# KELU1-0232.net
KiCad netlist of a schematic drawn in EAGLE
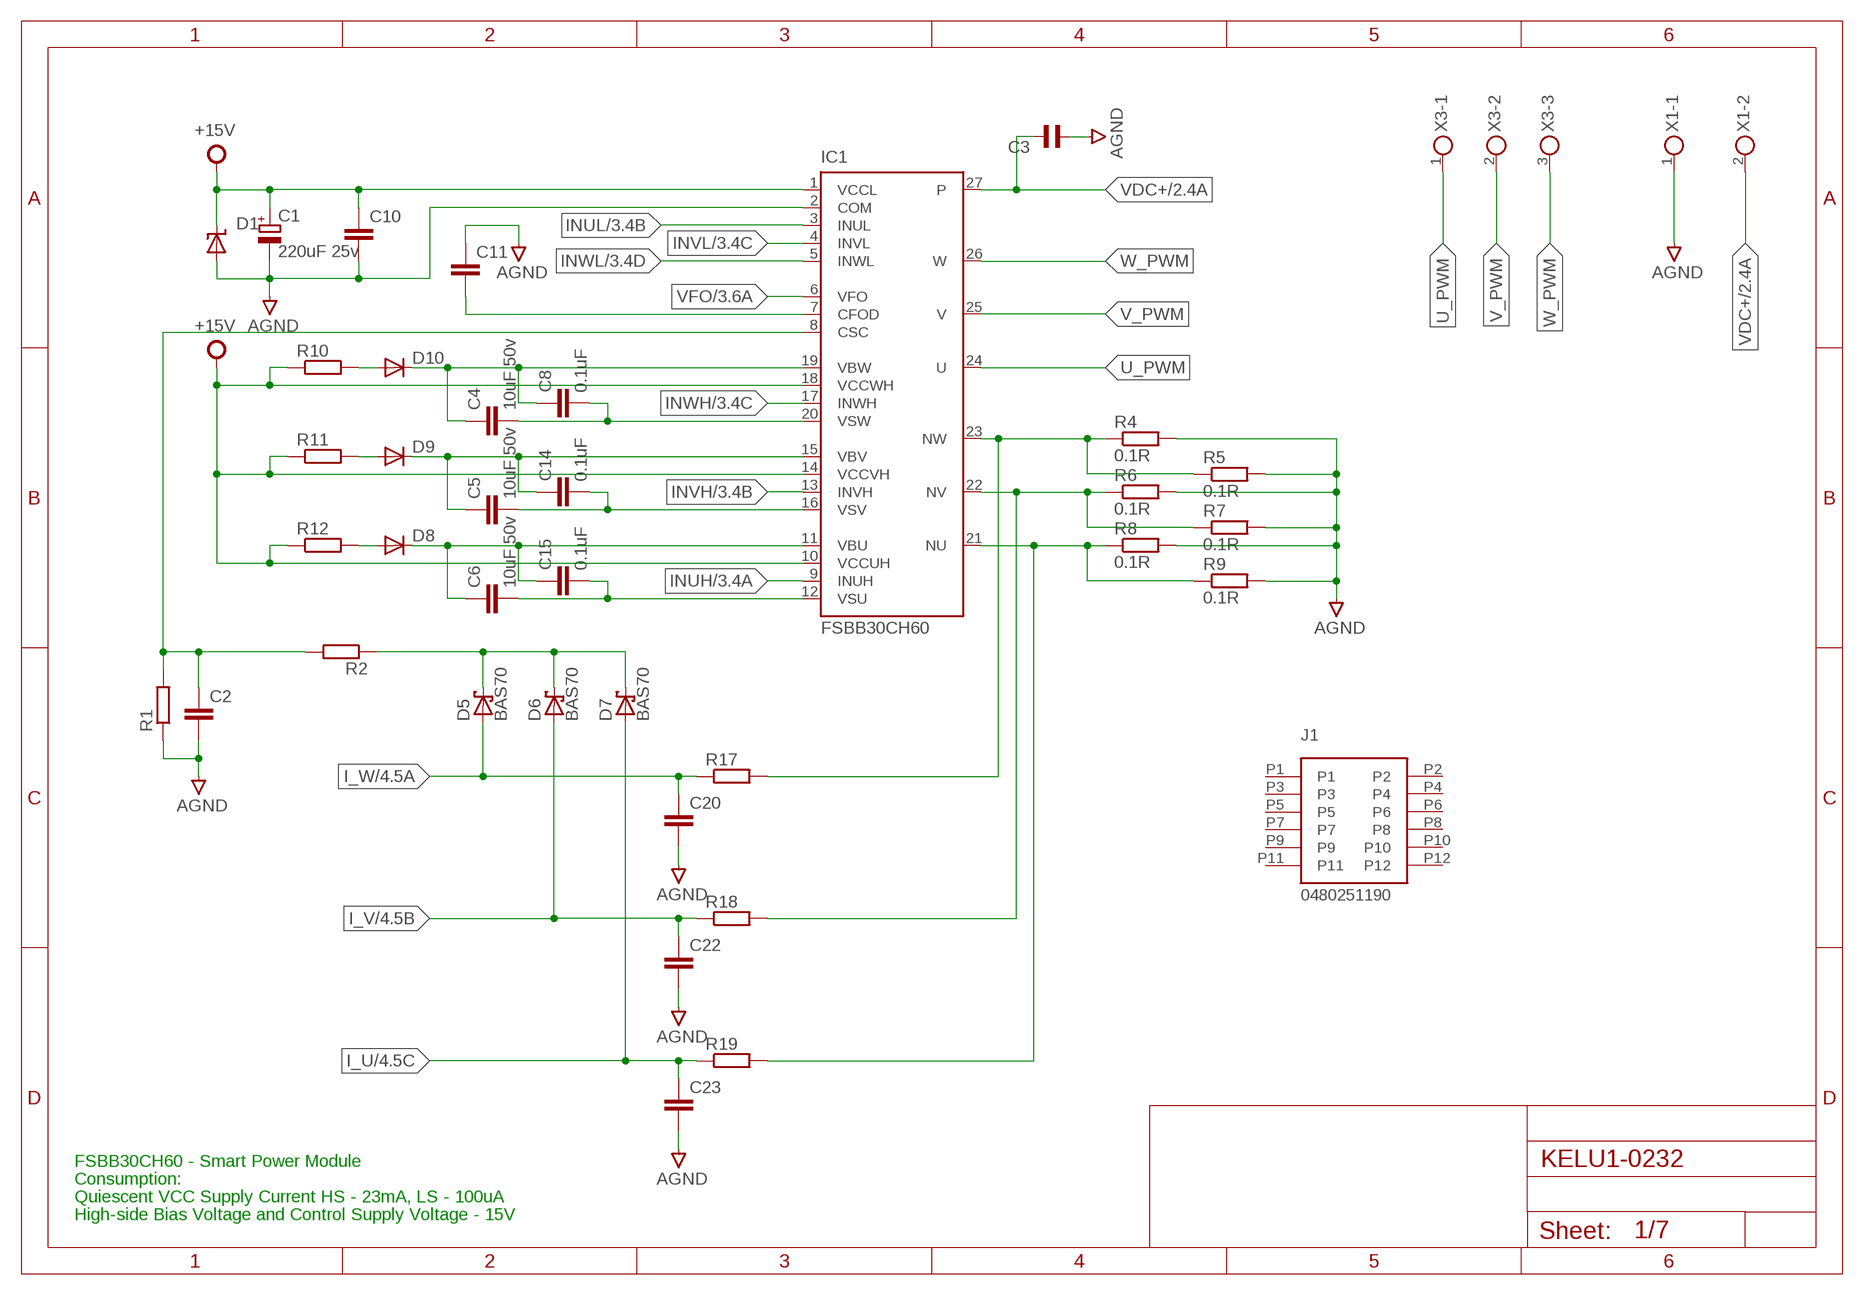
[diagram p0: schematic, sheet 1]
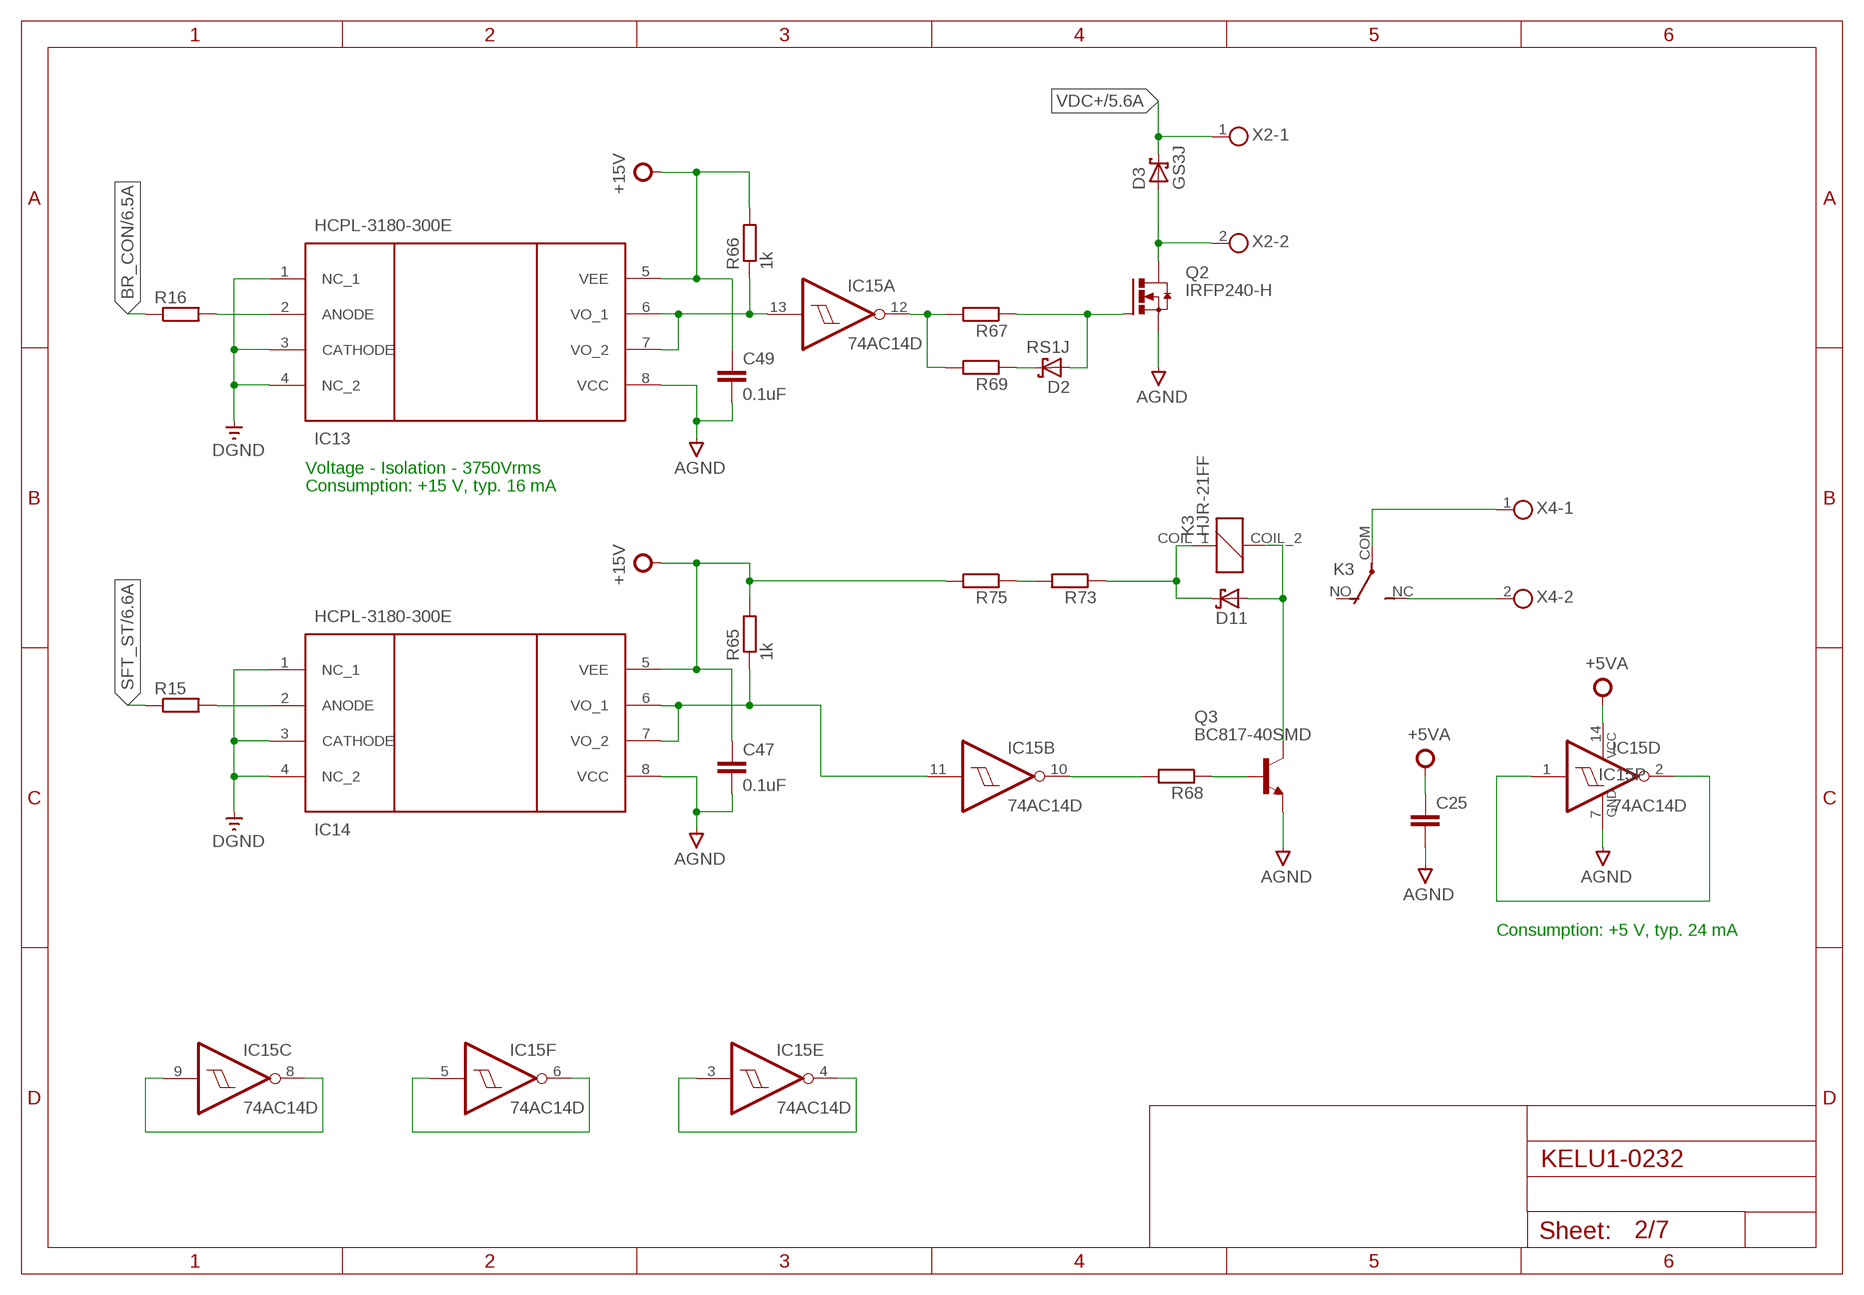
[diagram p1: schematic, sheet 2]
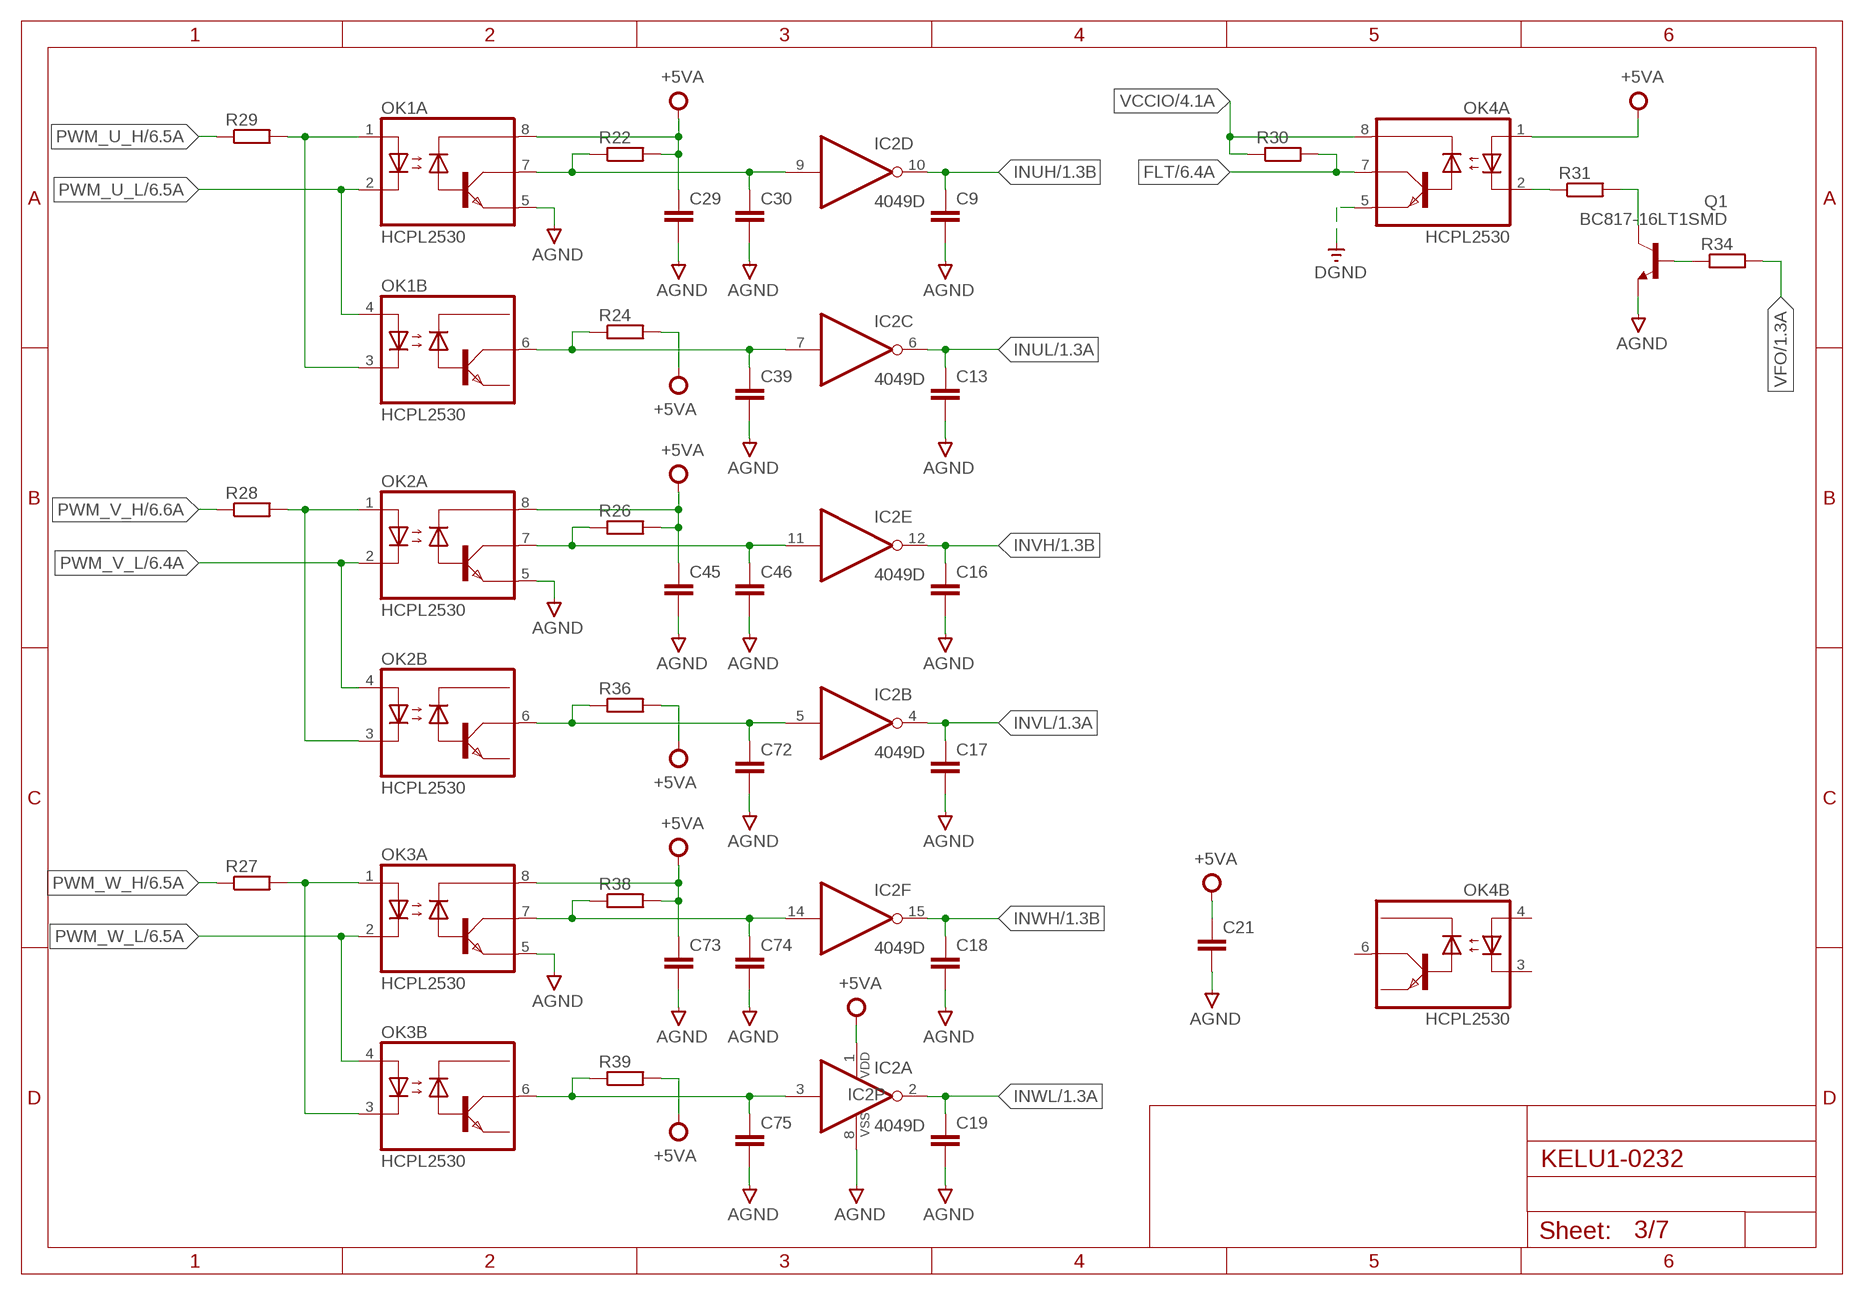
[diagram p2: schematic, sheet 3]
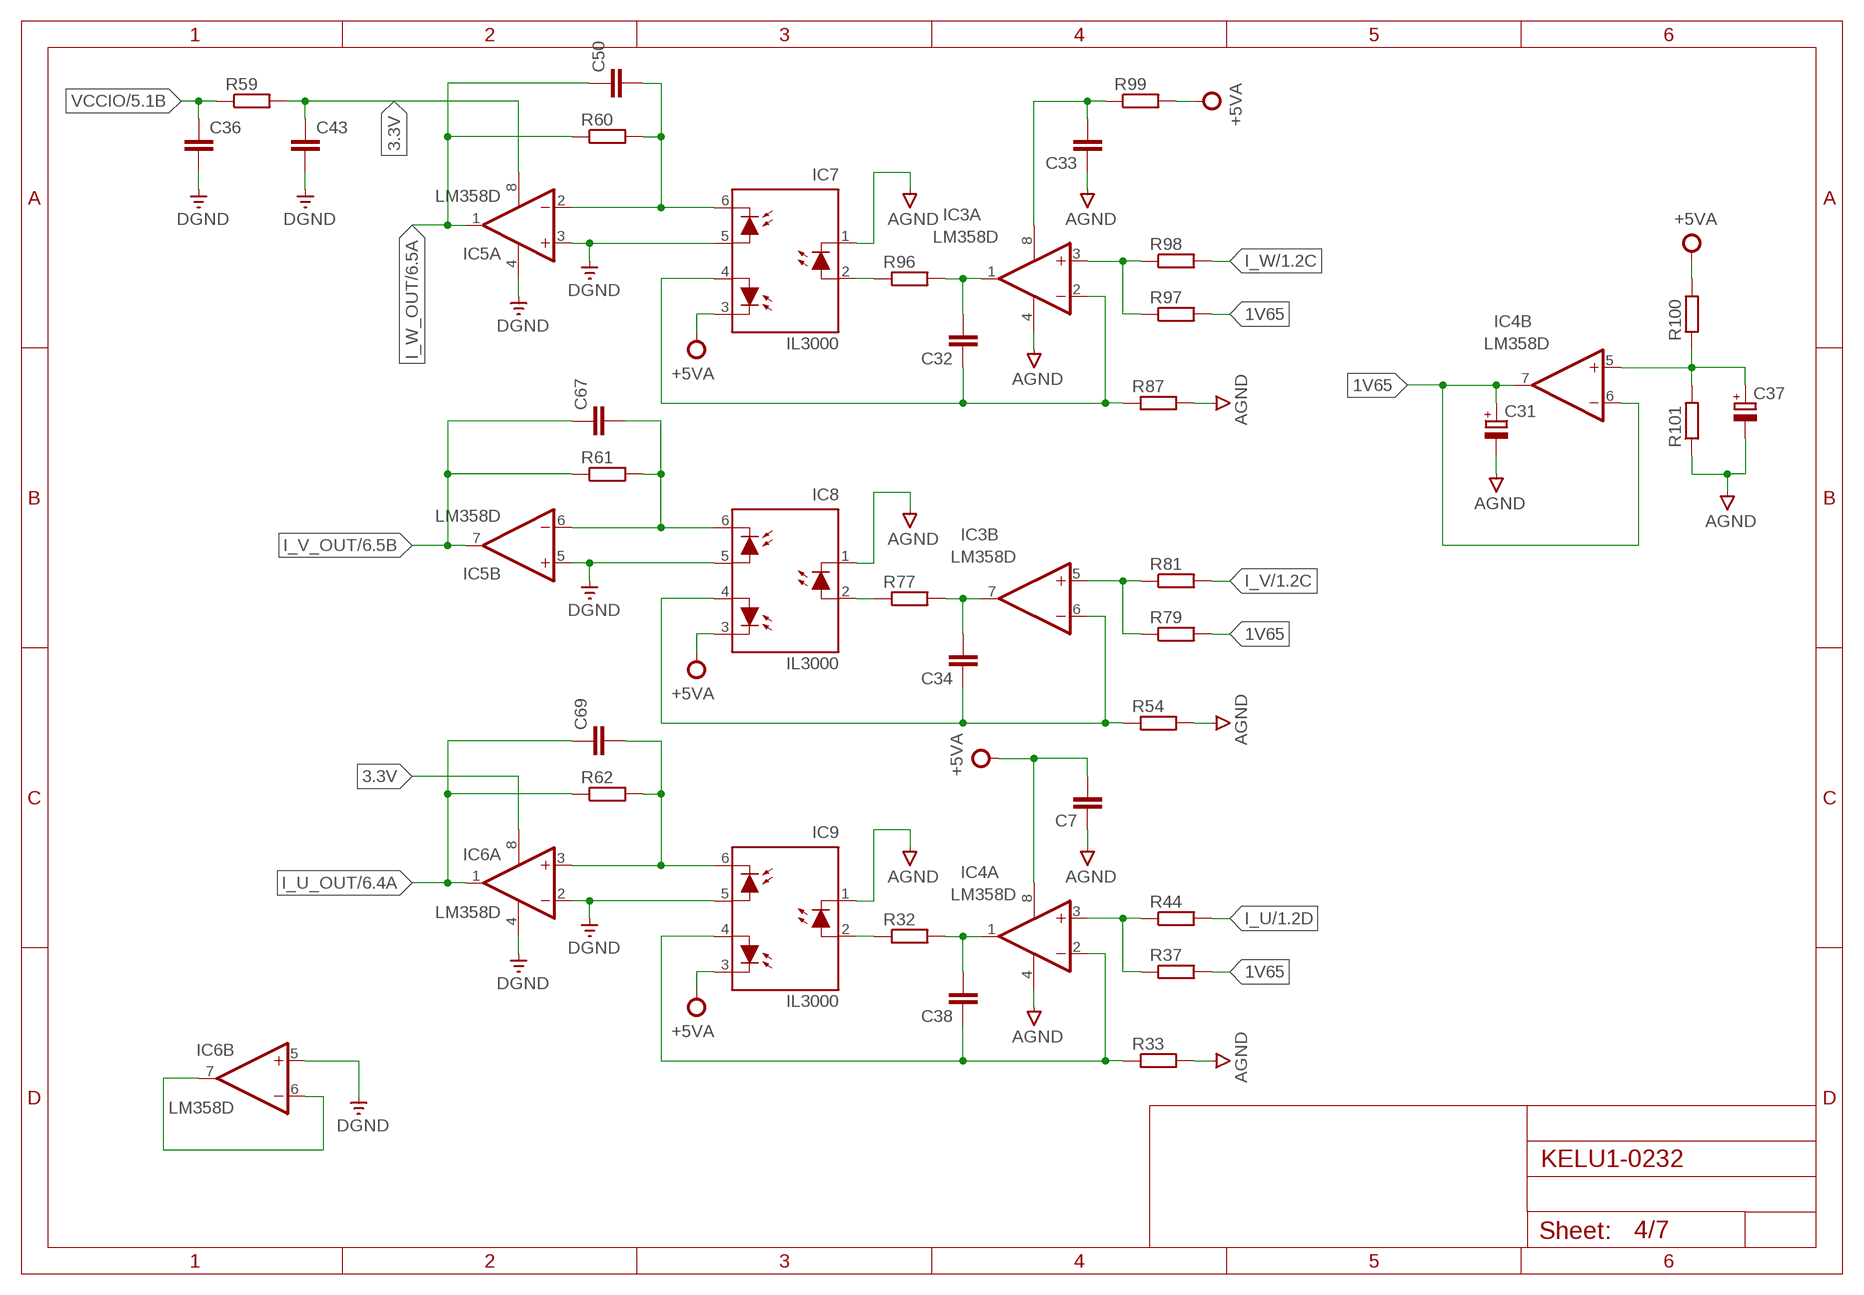
[diagram p3: schematic, sheet 4]
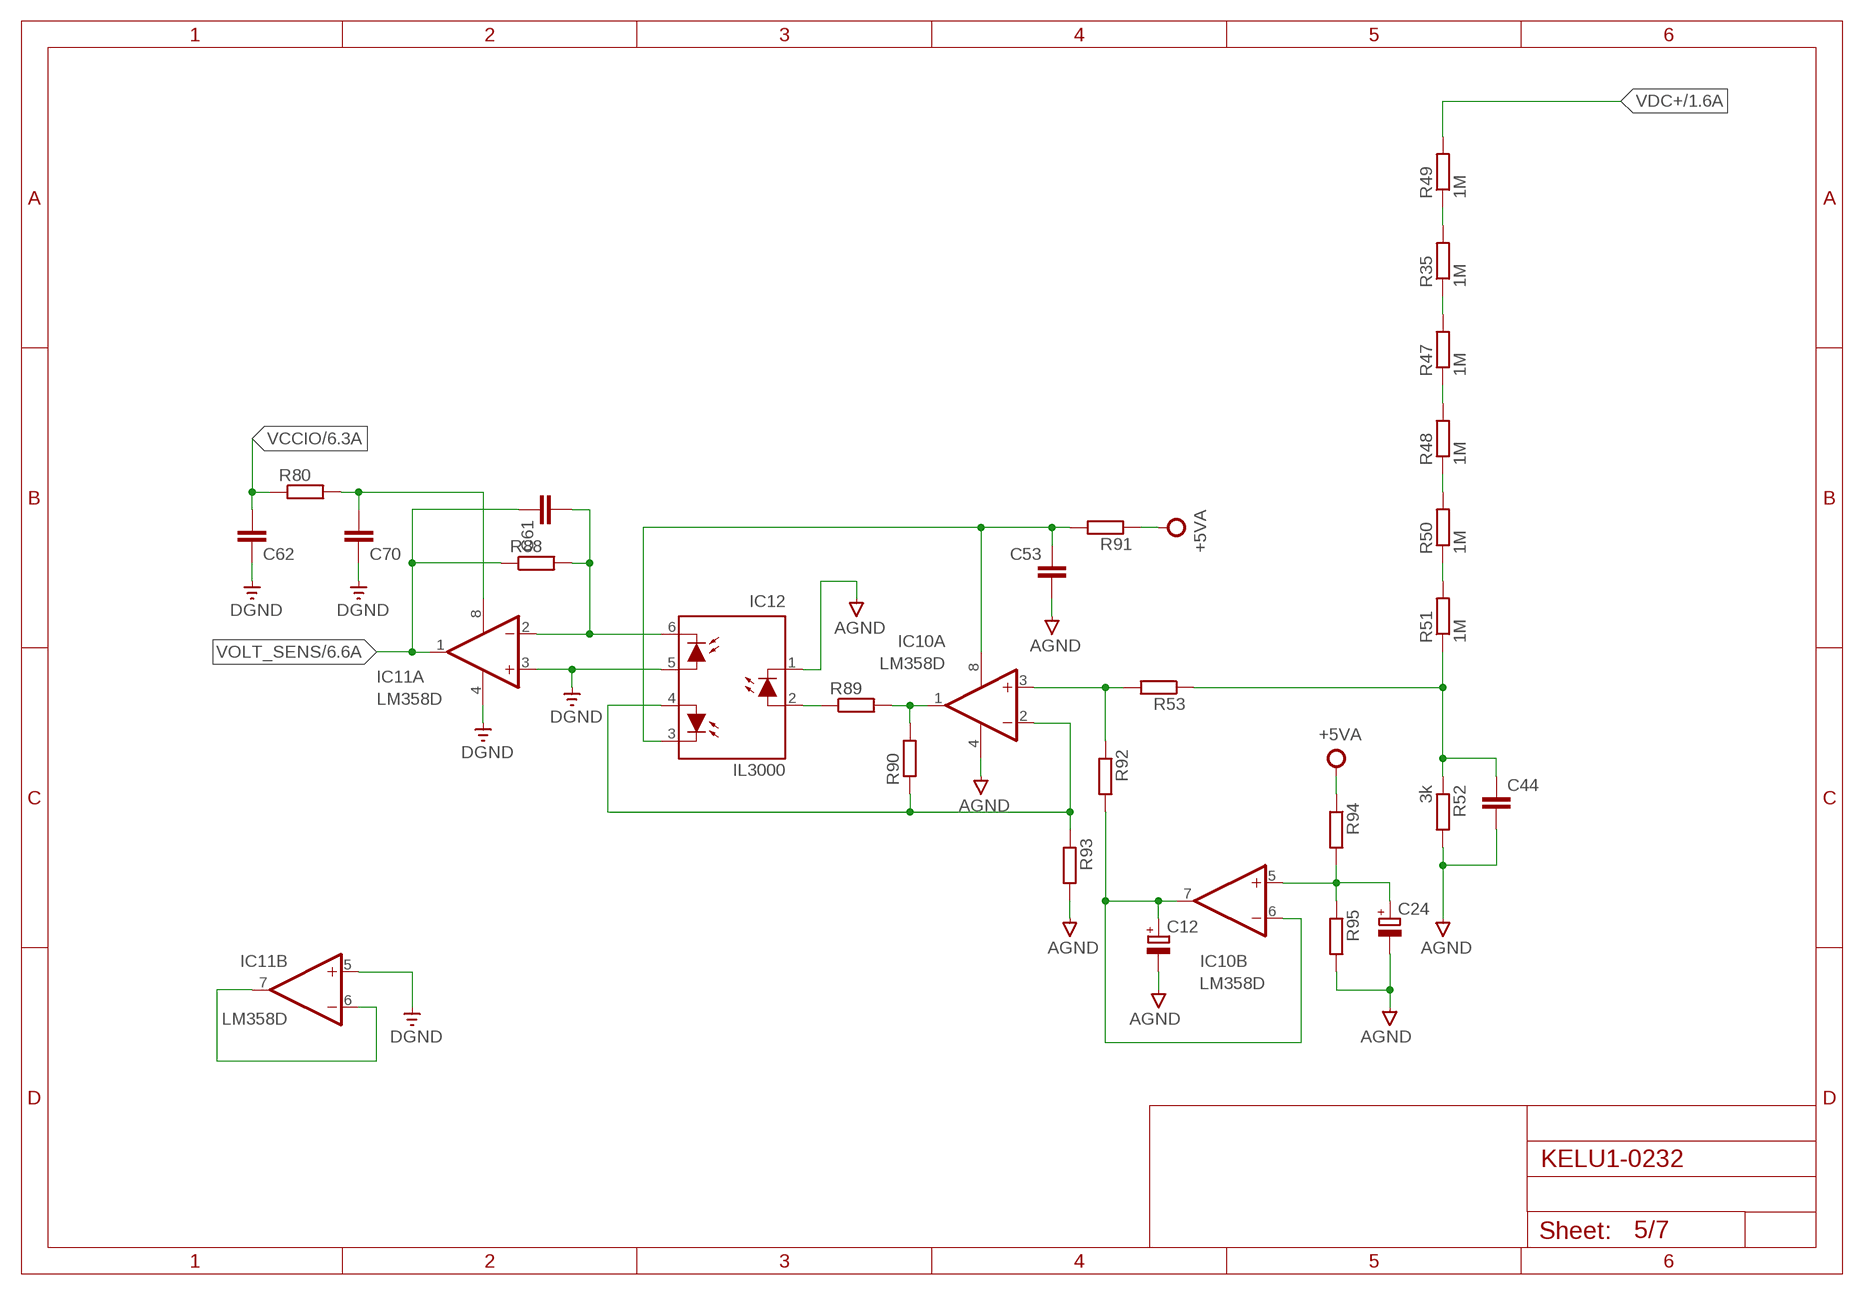
[diagram p4: schematic, sheet 5]
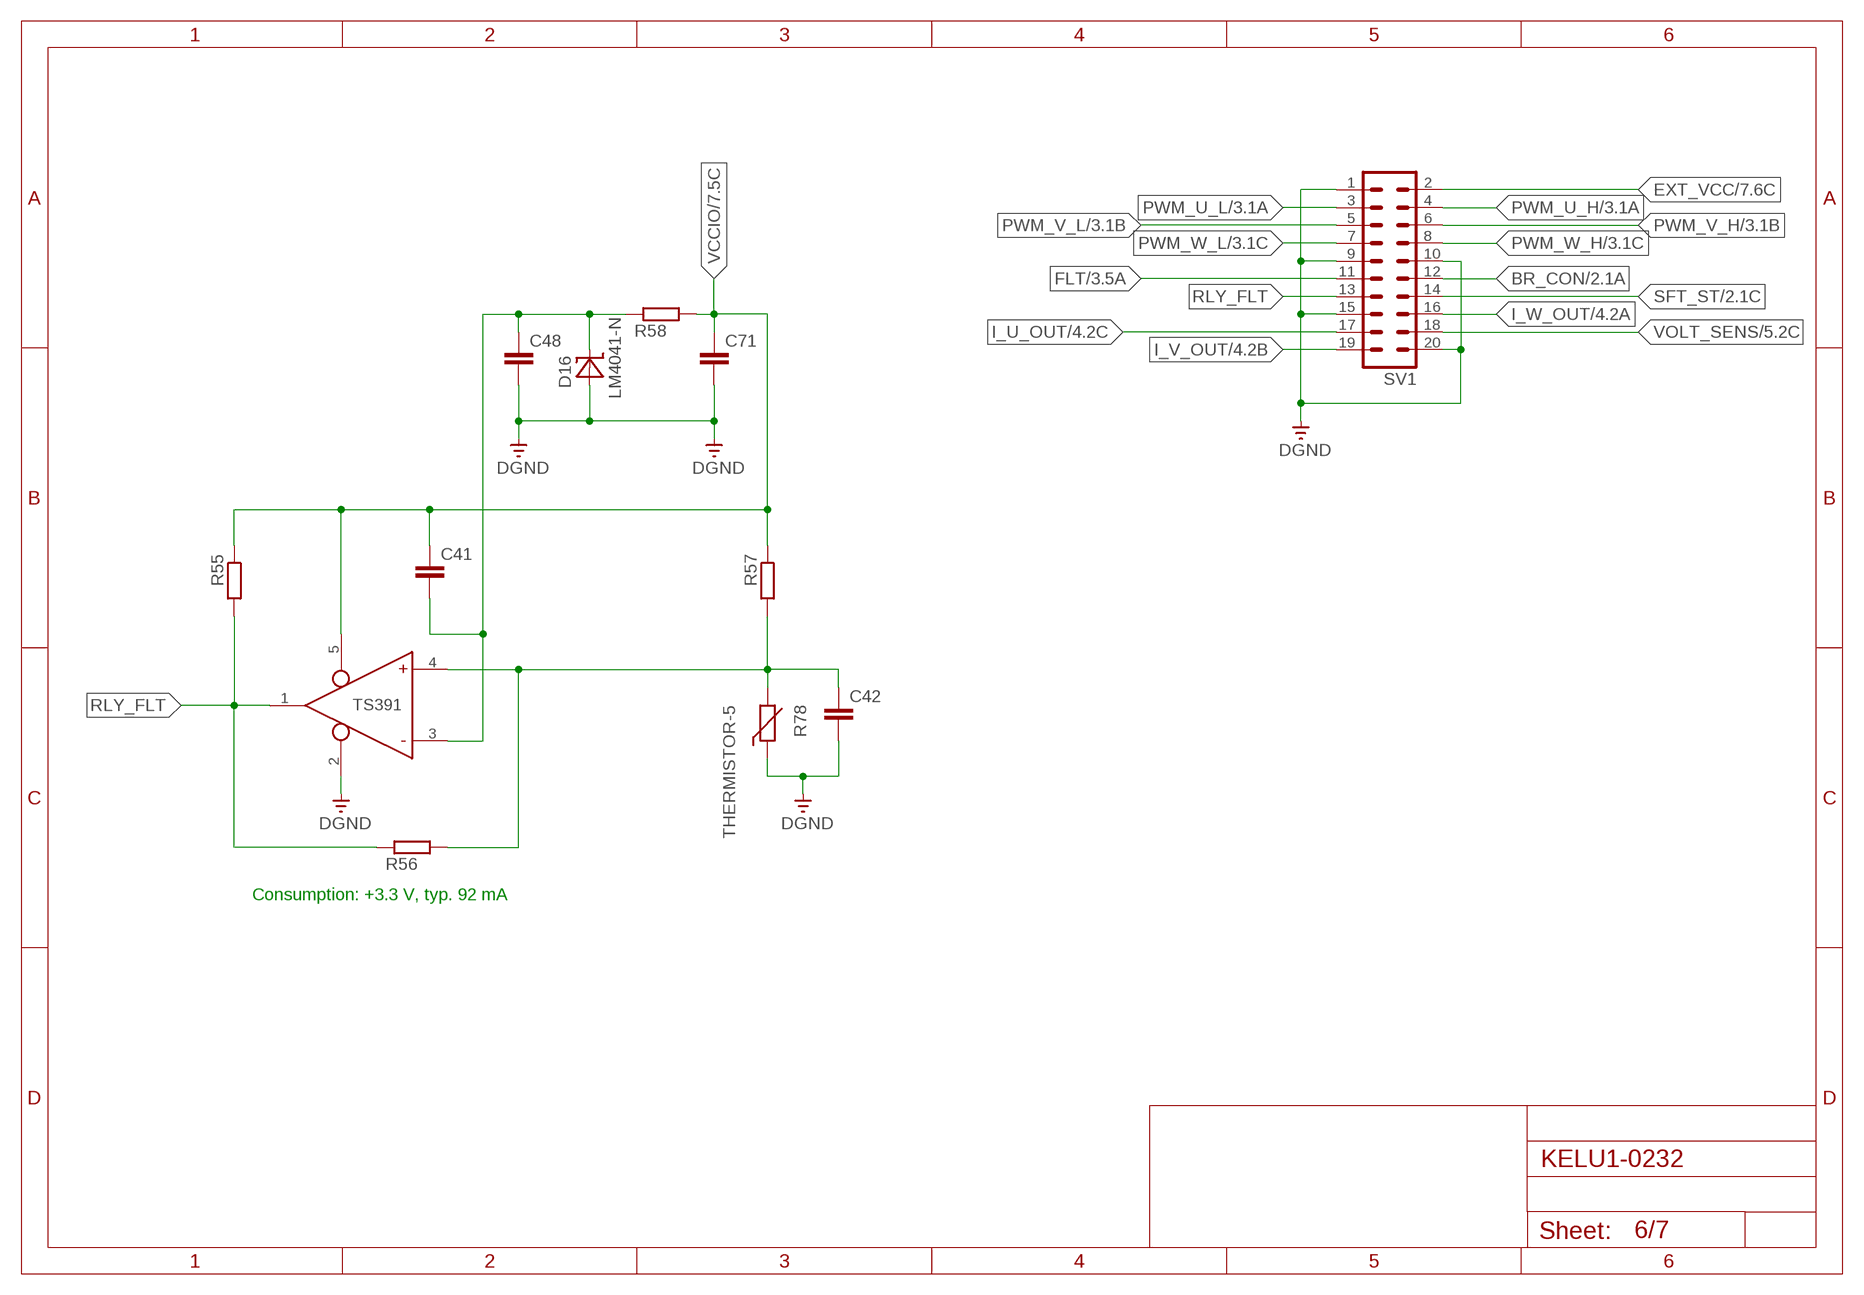
[diagram p5: schematic, sheet 6]
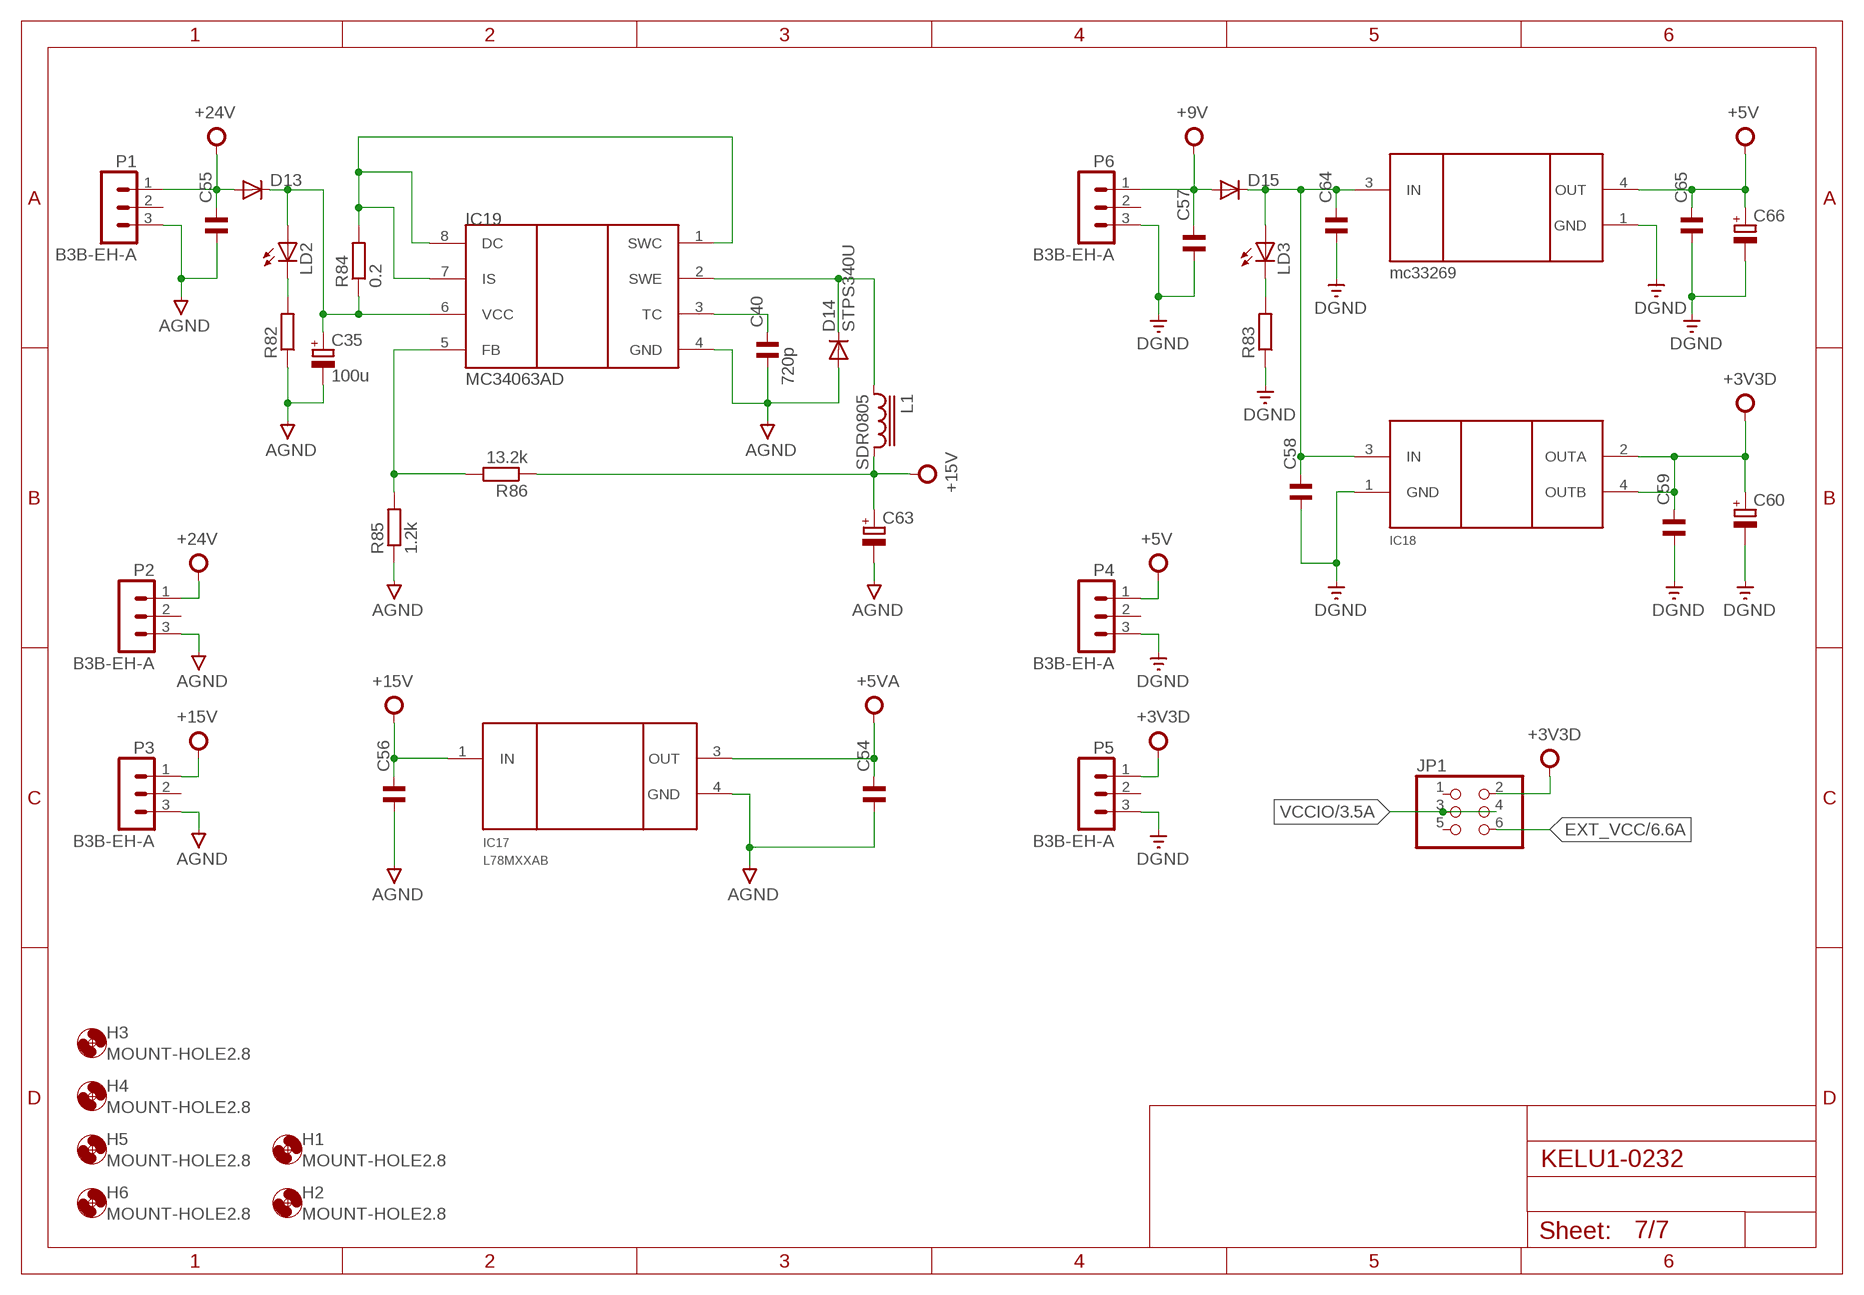
[diagram p6: schematic, sheet 7]

(export (version "E")
  (design (tool "Eeschema 10.0.6"))
  (components
    (comp (ref "C12")
      (value "CPOL-EUSMCB")
      (footprint "eagle-import:SMC_B")
      (libsource (lib "eagle-import") (part "resistor_CPOL-EUSMCB"))
    )
    (comp (ref "C24")
      (value "CPOL-EUSMCB")
      (footprint "eagle-import:SMC_B")
      (libsource (lib "eagle-import") (part "resistor_CPOL-EUSMCB"))
    )
    (comp (ref "C44")
      (value "C-EUC1206")
      (footprint "eagle-import:C1206")
      (libsource (lib "eagle-import") (part "resistor_C-EUC1206"))
    )
    (comp (ref "C53")
      (value "C-EUC0603")
      (footprint "eagle-import:C0603")
      (libsource (lib "eagle-import") (part "resistor_C-EUC0603"))
    )
    (comp (ref "C61")
      (value "C-EUC0603")
      (footprint "eagle-import:C0603")
      (libsource (lib "eagle-import") (part "resistor_C-EUC0603"))
    )
    (comp (ref "C62")
      (value "C-EUC0603")
      (footprint "eagle-import:C0603")
      (libsource (lib "eagle-import") (part "resistor_C-EUC0603"))
    )
    (comp (ref "C70")
      (value "C-EUC0603")
      (footprint "eagle-import:C0603")
      (libsource (lib "eagle-import") (part "resistor_C-EUC0603"))
    )
    (comp (ref "IC10")
      (value "LM358D")
      (footprint "eagle-import:SO08")
      (libsource (lib "eagle-import") (part "LM358D"))
    )
    (comp (ref "IC11")
      (value "LM358D")
      (footprint "eagle-import:SO08")
      (libsource (lib "eagle-import") (part "LM358D"))
    )
    (comp (ref "IC12")
      (value "IL3000")
      (footprint "eagle-import:DIL08-400")
      (libsource (lib "eagle-import") (part "IL3000"))
    )
    (comp (ref "R35")
      (value "1M")
      (footprint "eagle-import:M1206")
      (libsource (lib "eagle-import") (part "resistor_R-EU_M1206"))
    )
    (comp (ref "R47")
      (value "1M")
      (footprint "eagle-import:M1206")
      (libsource (lib "eagle-import") (part "resistor_R-EU_M1206"))
    )
    (comp (ref "R48")
      (value "1M")
      (footprint "eagle-import:M1206")
      (libsource (lib "eagle-import") (part "resistor_R-EU_M1206"))
    )
    (comp (ref "R49")
      (value "1M")
      (footprint "eagle-import:M1206")
      (libsource (lib "eagle-import") (part "resistor_R-EU_M1206"))
    )
    (comp (ref "R50")
      (value "1M")
      (footprint "eagle-import:M1206")
      (libsource (lib "eagle-import") (part "resistor_R-EU_M1206"))
    )
    (comp (ref "R51")
      (value "1M")
      (footprint "eagle-import:M1206")
      (libsource (lib "eagle-import") (part "resistor_R-EU_M1206"))
    )
    (comp (ref "R52")
      (value "3k")
      (footprint "eagle-import:M1206")
      (libsource (lib "eagle-import") (part "resistor_R-EU_M1206"))
    )
    (comp (ref "R53")
      (value "R-EU_R0603")
      (footprint "eagle-import:R0603")
      (libsource (lib "eagle-import") (part "resistor_R-EU_R0603"))
    )
    (comp (ref "R80")
      (value "R-EU_R0603")
      (footprint "eagle-import:R0603")
      (libsource (lib "eagle-import") (part "resistor_R-EU_R0603"))
    )
    (comp (ref "R88")
      (value "R-EU_R0603")
      (footprint "eagle-import:R0603")
      (libsource (lib "eagle-import") (part "resistor_R-EU_R0603"))
    )
    (comp (ref "R89")
      (value "R-EU_R0603")
      (footprint "eagle-import:R0603")
      (libsource (lib "eagle-import") (part "resistor_R-EU_R0603"))
    )
    (comp (ref "R90")
      (value "R-EU_R0603")
      (footprint "eagle-import:R0603")
      (libsource (lib "eagle-import") (part "resistor_R-EU_R0603"))
    )
    (comp (ref "R91")
      (value "R-EU_R0603")
      (footprint "eagle-import:R0603")
      (libsource (lib "eagle-import") (part "resistor_R-EU_R0603"))
    )
    (comp (ref "R92")
      (value "R-EU_R0603")
      (footprint "eagle-import:R0603")
      (libsource (lib "eagle-import") (part "resistor_R-EU_R0603"))
    )
    (comp (ref "R93")
      (value "R-EU_R0603")
      (footprint "eagle-import:R0603")
      (libsource (lib "eagle-import") (part "resistor_R-EU_R0603"))
    )
    (comp (ref "R94")
      (value "R-EU_R0603")
      (footprint "eagle-import:R0603")
      (libsource (lib "eagle-import") (part "resistor_R-EU_R0603"))
    )
    (comp (ref "R95")
      (value "R-EU_R0603")
      (footprint "eagle-import:R0603")
      (libsource (lib "eagle-import") (part "resistor_R-EU_R0603"))
    )
    (comp (ref "C7")
      (value "C-EUC0603")
      (footprint "eagle-import:C0603")
      (libsource (lib "eagle-import") (part "resistor_C-EUC0603"))
    )
    (comp (ref "C31")
      (value "CPOL-EUSMCB")
      (footprint "eagle-import:SMC_B")
      (libsource (lib "eagle-import") (part "resistor_CPOL-EUSMCB"))
    )
    (comp (ref "C32")
      (value "C-EUC0603")
      (footprint "eagle-import:C0603")
      (libsource (lib "eagle-import") (part "resistor_C-EUC0603"))
    )
    (comp (ref "C33")
      (value "C-EUC0603")
      (footprint "eagle-import:C0603")
      (libsource (lib "eagle-import") (part "resistor_C-EUC0603"))
    )
    (comp (ref "C34")
      (value "C-EUC0603")
      (footprint "eagle-import:C0603")
      (libsource (lib "eagle-import") (part "resistor_C-EUC0603"))
    )
    (comp (ref "C36")
      (value "C-EUC0603")
      (footprint "eagle-import:C0603")
      (libsource (lib "eagle-import") (part "resistor_C-EUC0603"))
    )
    (comp (ref "C37")
      (value "CPOL-EUSMCB")
      (footprint "eagle-import:SMC_B")
      (libsource (lib "eagle-import") (part "resistor_CPOL-EUSMCB"))
    )
    (comp (ref "C38")
      (value "C-EUC0603")
      (footprint "eagle-import:C0603")
      (libsource (lib "eagle-import") (part "resistor_C-EUC0603"))
    )
    (comp (ref "C43")
      (value "C-EUC0603")
      (footprint "eagle-import:C0603")
      (libsource (lib "eagle-import") (part "resistor_C-EUC0603"))
    )
    (comp (ref "C50")
      (value "C-EUC0603")
      (footprint "eagle-import:C0603")
      (libsource (lib "eagle-import") (part "resistor_C-EUC0603"))
    )
    (comp (ref "C67")
      (value "C-EUC0603")
      (footprint "eagle-import:C0603")
      (libsource (lib "eagle-import") (part "resistor_C-EUC0603"))
    )
    (comp (ref "C69")
      (value "C-EUC0603")
      (footprint "eagle-import:C0603")
      (libsource (lib "eagle-import") (part "resistor_C-EUC0603"))
    )
    (comp (ref "IC3")
      (value "LM358D")
      (footprint "eagle-import:SO08")
      (libsource (lib "eagle-import") (part "LM358D"))
    )
    (comp (ref "IC4")
      (value "LM358D")
      (footprint "eagle-import:SO08")
      (libsource (lib "eagle-import") (part "LM358D"))
    )
    (comp (ref "IC5")
      (value "LM358D")
      (footprint "eagle-import:SO08")
      (libsource (lib "eagle-import") (part "LM358D"))
    )
    (comp (ref "IC6")
      (value "LM358D")
      (footprint "eagle-import:SO08")
      (libsource (lib "eagle-import") (part "LM358D"))
    )
    (comp (ref "IC7")
      (value "IL3000")
      (footprint "eagle-import:DIL08-400")
      (libsource (lib "eagle-import") (part "IL3000"))
    )
    (comp (ref "IC8")
      (value "IL3000")
      (footprint "eagle-import:DIL08-400")
      (libsource (lib "eagle-import") (part "IL3000"))
    )
    (comp (ref "IC9")
      (value "IL3000")
      (footprint "eagle-import:DIL08-400")
      (libsource (lib "eagle-import") (part "IL3000"))
    )
    (comp (ref "R32")
      (value "R-EU_R0603")
      (footprint "eagle-import:R0603")
      (libsource (lib "eagle-import") (part "resistor_R-EU_R0603"))
    )
    (comp (ref "R33")
      (value "R-EU_R0603")
      (footprint "eagle-import:R0603")
      (libsource (lib "eagle-import") (part "resistor_R-EU_R0603"))
    )
    (comp (ref "R37")
      (value "R-EU_R0603")
      (footprint "eagle-import:R0603")
      (libsource (lib "eagle-import") (part "resistor_R-EU_R0603"))
    )
    (comp (ref "R44")
      (value "R-EU_R0603")
      (footprint "eagle-import:R0603")
      (libsource (lib "eagle-import") (part "resistor_R-EU_R0603"))
    )
    (comp (ref "R54")
      (value "R-EU_R0603")
      (footprint "eagle-import:R0603")
      (libsource (lib "eagle-import") (part "resistor_R-EU_R0603"))
    )
    (comp (ref "R59")
      (value "R-EU_R0603")
      (footprint "eagle-import:R0603")
      (libsource (lib "eagle-import") (part "resistor_R-EU_R0603"))
    )
    (comp (ref "R60")
      (value "R-EU_R0603")
      (footprint "eagle-import:R0603")
      (libsource (lib "eagle-import") (part "resistor_R-EU_R0603"))
    )
    (comp (ref "R61")
      (value "R-EU_R0603")
      (footprint "eagle-import:R0603")
      (libsource (lib "eagle-import") (part "resistor_R-EU_R0603"))
    )
    (comp (ref "R62")
      (value "R-EU_R0603")
      (footprint "eagle-import:R0603")
      (libsource (lib "eagle-import") (part "resistor_R-EU_R0603"))
    )
    (comp (ref "R77")
      (value "R-EU_R0603")
      (footprint "eagle-import:R0603")
      (libsource (lib "eagle-import") (part "resistor_R-EU_R0603"))
    )
    (comp (ref "R79")
      (value "R-EU_R0603")
      (footprint "eagle-import:R0603")
      (libsource (lib "eagle-import") (part "resistor_R-EU_R0603"))
    )
    (comp (ref "R81")
      (value "R-EU_R0603")
      (footprint "eagle-import:R0603")
      (libsource (lib "eagle-import") (part "resistor_R-EU_R0603"))
    )
    (comp (ref "R87")
      (value "R-EU_R0603")
      (footprint "eagle-import:R0603")
      (libsource (lib "eagle-import") (part "resistor_R-EU_R0603"))
    )
    (comp (ref "R96")
      (value "R-EU_R0603")
      (footprint "eagle-import:R0603")
      (libsource (lib "eagle-import") (part "resistor_R-EU_R0603"))
    )
    (comp (ref "R97")
      (value "R-EU_R0603")
      (footprint "eagle-import:R0603")
      (libsource (lib "eagle-import") (part "resistor_R-EU_R0603"))
    )
    (comp (ref "R98")
      (value "R-EU_R0603")
      (footprint "eagle-import:R0603")
      (libsource (lib "eagle-import") (part "resistor_R-EU_R0603"))
    )
    (comp (ref "R99")
      (value "R-EU_R0603")
      (footprint "eagle-import:R0603")
      (libsource (lib "eagle-import") (part "resistor_R-EU_R0603"))
    )
    (comp (ref "R100")
      (value "R-EU_R0603")
      (footprint "eagle-import:R0603")
      (libsource (lib "eagle-import") (part "resistor_R-EU_R0603"))
    )
    (comp (ref "R101")
      (value "R-EU_R0603")
      (footprint "eagle-import:R0603")
      (libsource (lib "eagle-import") (part "resistor_R-EU_R0603"))
    )
    (comp (ref "C41")
      (value "C-EUC0603")
      (footprint "eagle-import:C0603")
      (libsource (lib "eagle-import") (part "resistor_C-EUC0603"))
    )
    (comp (ref "C42")
      (value "C-EUC0603")
      (footprint "eagle-import:C0603")
      (libsource (lib "eagle-import") (part "resistor_C-EUC0603"))
    )
    (comp (ref "C48")
      (value "C-EUC0603")
      (footprint "eagle-import:C0603")
      (libsource (lib "eagle-import") (part "resistor_C-EUC0603"))
    )
    (comp (ref "C71")
      (value "C-EUC0603")
      (footprint "eagle-import:C0603")
      (libsource (lib "eagle-import") (part "resistor_C-EUC0603"))
    )
    (comp (ref "D16")
      (value "LM4041-N")
      (footprint "eagle-import:SOT23")
      (libsource (lib "eagle-import") (part "LM4041-N"))
    )
    (comp (ref "R55")
      (value "R-EU_R0603")
      (footprint "eagle-import:R0603")
      (libsource (lib "eagle-import") (part "resistor_R-EU_R0603"))
    )
    (comp (ref "R56")
      (value "R-EU_R0603")
      (footprint "eagle-import:R0603")
      (libsource (lib "eagle-import") (part "resistor_R-EU_R0603"))
    )
    (comp (ref "R57")
      (value "R-EU_R0603")
      (footprint "eagle-import:R0603")
      (libsource (lib "eagle-import") (part "resistor_R-EU_R0603"))
    )
    (comp (ref "R58")
      (value "R-EU_R0603")
      (footprint "eagle-import:R0603")
      (libsource (lib "eagle-import") (part "resistor_R-EU_R0603"))
    )
    (comp (ref "R78")
      (value "THERMISTOR-5")
      (footprint "eagle-import:R-5")
      (libsource (lib "eagle-import") (part "THERMISTOR-5"))
    )
    (comp (ref "SV1")
      (value "ML20")
      (footprint "eagle-import:ML20")
      (libsource (lib "eagle-import") (part "ML20"))
    )
    (comp (ref "U$2")
      (value "TS391")
      (footprint "eagle-import:SOT23-5")
      (libsource (lib "eagle-import") (part "TS391"))
    )
    (comp (ref "C9")
      (value "C-EUC0603")
      (footprint "eagle-import:C0603")
      (libsource (lib "eagle-import") (part "resistor_C-EUC0603"))
    )
    (comp (ref "C13")
      (value "C-EUC0603")
      (footprint "eagle-import:C0603")
      (libsource (lib "eagle-import") (part "resistor_C-EUC0603"))
    )
    (comp (ref "C16")
      (value "C-EUC0603")
      (footprint "eagle-import:C0603")
      (libsource (lib "eagle-import") (part "resistor_C-EUC0603"))
    )
    (comp (ref "C17")
      (value "C-EUC0603")
      (footprint "eagle-import:C0603")
      (libsource (lib "eagle-import") (part "resistor_C-EUC0603"))
    )
    (comp (ref "C18")
      (value "C-EUC0603")
      (footprint "eagle-import:C0603")
      (libsource (lib "eagle-import") (part "resistor_C-EUC0603"))
    )
    (comp (ref "C19")
      (value "C-EUC0603")
      (footprint "eagle-import:C0603")
      (libsource (lib "eagle-import") (part "resistor_C-EUC0603"))
    )
    (comp (ref "C21")
      (value "C-EUC0603")
      (footprint "eagle-import:C0603")
      (libsource (lib "eagle-import") (part "resistor_C-EUC0603"))
    )
    (comp (ref "C29")
      (value "C-EUC0603")
      (footprint "eagle-import:C0603")
      (libsource (lib "eagle-import") (part "resistor_C-EUC0603"))
    )
    (comp (ref "C30")
      (value "C-EUC0603")
      (footprint "eagle-import:C0603")
      (libsource (lib "eagle-import") (part "resistor_C-EUC0603"))
    )
    (comp (ref "C39")
      (value "C-EUC0603")
      (footprint "eagle-import:C0603")
      (libsource (lib "eagle-import") (part "resistor_C-EUC0603"))
    )
    (comp (ref "C45")
      (value "C-EUC0603")
      (footprint "eagle-import:C0603")
      (libsource (lib "eagle-import") (part "resistor_C-EUC0603"))
    )
    (comp (ref "C46")
      (value "C-EUC0603")
      (footprint "eagle-import:C0603")
      (libsource (lib "eagle-import") (part "resistor_C-EUC0603"))
    )
    (comp (ref "C72")
      (value "C-EUC0603")
      (footprint "eagle-import:C0603")
      (libsource (lib "eagle-import") (part "resistor_C-EUC0603"))
    )
    (comp (ref "C73")
      (value "C-EUC0603")
      (footprint "eagle-import:C0603")
      (libsource (lib "eagle-import") (part "resistor_C-EUC0603"))
    )
    (comp (ref "C74")
      (value "C-EUC0603")
      (footprint "eagle-import:C0603")
      (libsource (lib "eagle-import") (part "resistor_C-EUC0603"))
    )
    (comp (ref "C75")
      (value "C-EUC0603")
      (footprint "eagle-import:C0603")
      (libsource (lib "eagle-import") (part "resistor_C-EUC0603"))
    )
    (comp (ref "IC2")
      (value "4049D")
      (footprint "eagle-import:SO16")
      (libsource (lib "eagle-import") (part "4049D"))
    )
    (comp (ref "OK1")
      (value "HCPL2530")
      (footprint "eagle-import:DIL08")
      (fields (field (name "MF") "AGILENT TECHNOLOGIES") (field (name "MPN") "HCPL-2530-000E"))
      (libsource (lib "eagle-import") (part "HCPL2530"))
    )
    (comp (ref "OK2")
      (value "HCPL2530")
      (footprint "eagle-import:DIL08")
      (fields (field (name "MF") "AGILENT TECHNOLOGIES") (field (name "MPN") "HCPL-2530-000E"))
      (libsource (lib "eagle-import") (part "HCPL2530"))
    )
    (comp (ref "OK3")
      (value "HCPL2530")
      (footprint "eagle-import:DIL08")
      (fields (field (name "MF") "AGILENT TECHNOLOGIES") (field (name "MPN") "HCPL-2530-000E"))
      (libsource (lib "eagle-import") (part "HCPL2530"))
    )
    (comp (ref "OK4")
      (value "HCPL2530")
      (footprint "eagle-import:DIL08")
      (fields (field (name "MF") "AGILENT TECHNOLOGIES") (field (name "MPN") "HCPL-2530-000E"))
      (libsource (lib "eagle-import") (part "HCPL2530"))
    )
    (comp (ref "Q1")
      (value "BC817-16LT1SMD")
      (footprint "eagle-import:SOT23-BEC")
      (libsource (lib "eagle-import") (part "BC817SMD-16LT1"))
    )
    (comp (ref "R22")
      (value "R-EU_R0603")
      (footprint "eagle-import:R0603")
      (libsource (lib "eagle-import") (part "resistor_R-EU_R0603"))
    )
    (comp (ref "R24")
      (value "R-EU_R0603")
      (footprint "eagle-import:R0603")
      (libsource (lib "eagle-import") (part "resistor_R-EU_R0603"))
    )
    (comp (ref "R26")
      (value "R-EU_R0603")
      (footprint "eagle-import:R0603")
      (libsource (lib "eagle-import") (part "resistor_R-EU_R0603"))
    )
    (comp (ref "R27")
      (value "R-EU_R0603")
      (footprint "eagle-import:R0603")
      (libsource (lib "eagle-import") (part "resistor_R-EU_R0603"))
    )
    (comp (ref "R28")
      (value "R-EU_R0603")
      (footprint "eagle-import:R0603")
      (libsource (lib "eagle-import") (part "resistor_R-EU_R0603"))
    )
    (comp (ref "R29")
      (value "R-EU_R0603")
      (footprint "eagle-import:R0603")
      (libsource (lib "eagle-import") (part "resistor_R-EU_R0603"))
    )
    (comp (ref "R30")
      (value "R-EU_R0603")
      (footprint "eagle-import:R0603")
      (libsource (lib "eagle-import") (part "resistor_R-EU_R0603"))
    )
    (comp (ref "R31")
      (value "R-EU_R0603")
      (footprint "eagle-import:R0603")
      (libsource (lib "eagle-import") (part "resistor_R-EU_R0603"))
    )
    (comp (ref "R34")
      (value "R-EU_R0603")
      (footprint "eagle-import:R0603")
      (libsource (lib "eagle-import") (part "resistor_R-EU_R0603"))
    )
    (comp (ref "R36")
      (value "R-EU_R0603")
      (footprint "eagle-import:R0603")
      (libsource (lib "eagle-import") (part "resistor_R-EU_R0603"))
    )
    (comp (ref "R38")
      (value "R-EU_R0603")
      (footprint "eagle-import:R0603")
      (libsource (lib "eagle-import") (part "resistor_R-EU_R0603"))
    )
    (comp (ref "R39")
      (value "R-EU_R0603")
      (footprint "eagle-import:R0603")
      (libsource (lib "eagle-import") (part "resistor_R-EU_R0603"))
    )
    (comp (ref "C35")
      (value "100u")
      (footprint "eagle-import:175TMP-0810")
      (libsource (lib "eagle-import") (part "CPOL-EU175TMP-0810"))
    )
    (comp (ref "C40")
      (value "720p")
      (footprint "eagle-import:C0805")
      (libsource (lib "eagle-import") (part "C-EUC0805"))
    )
    (comp (ref "C54")
      (value "C-EUC0805")
      (footprint "eagle-import:C0805")
      (libsource (lib "eagle-import") (part "C-EUC0805"))
    )
    (comp (ref "C55")
      (value "C-EUC0805")
      (footprint "eagle-import:C0805")
      (libsource (lib "eagle-import") (part "C-EUC0805"))
    )
    (comp (ref "C56")
      (value "C-EUC0805")
      (footprint "eagle-import:C0805")
      (libsource (lib "eagle-import") (part "C-EUC0805"))
    )
    (comp (ref "C57")
      (value "C-EUC0805")
      (footprint "eagle-import:C0805")
      (libsource (lib "eagle-import") (part "C-EUC0805"))
    )
    (comp (ref "C58")
      (value "C-EUC0805")
      (footprint "eagle-import:C0805")
      (libsource (lib "eagle-import") (part "C-EUC0805"))
    )
    (comp (ref "C59")
      (value "C-EUC0805")
      (footprint "eagle-import:C0805")
      (libsource (lib "eagle-import") (part "C-EUC0805"))
    )
    (comp (ref "C60")
      (value "CPOL-EUA/3216-18R")
      (footprint "eagle-import:A_3216-18R")
      (libsource (lib "eagle-import") (part "CPOL-EUA/3216-18R"))
    )
    (comp (ref "C63")
      (value "CPOL-EU175TMP-0810")
      (footprint "eagle-import:175TMP-0810")
      (libsource (lib "eagle-import") (part "CPOL-EU175TMP-0810"))
    )
    (comp (ref "C64")
      (value "C-EUC0805")
      (footprint "eagle-import:C0805")
      (libsource (lib "eagle-import") (part "C-EUC0805"))
    )
    (comp (ref "C65")
      (value "C-EUC0805")
      (footprint "eagle-import:C0805")
      (libsource (lib "eagle-import") (part "C-EUC0805"))
    )
    (comp (ref "C66")
      (value "CPOL-EUA/3216-18R")
      (footprint "eagle-import:A_3216-18R")
      (libsource (lib "eagle-import") (part "CPOL-EUA/3216-18R"))
    )
    (comp (ref "D13")
      (value "DIODE-SMB")
      (footprint "eagle-import:SMB")
      (libsource (lib "eagle-import") (part "DIODE-SMB"))
    )
    (comp (ref "D14")
      (value "STPS340U")
      (footprint "eagle-import:SMB")
      (libsource (lib "eagle-import") (part "DIODE-SMB"))
    )
    (comp (ref "D15")
      (value "DIODE-SMB")
      (footprint "eagle-import:SMB")
      (libsource (lib "eagle-import") (part "DIODE-SMB"))
    )
    (comp (ref "H1")
      (value "MOUNT-HOLE2.8")
      (footprint "eagle-import:2,8")
      (libsource (lib "eagle-import") (part "MOUNT-HOLE2.8"))
    )
    (comp (ref "H2")
      (value "MOUNT-HOLE2.8")
      (footprint "eagle-import:2,8")
      (libsource (lib "eagle-import") (part "MOUNT-HOLE2.8"))
    )
    (comp (ref "H3")
      (value "MOUNT-HOLE2.8")
      (footprint "eagle-import:2,8")
      (libsource (lib "eagle-import") (part "MOUNT-HOLE2.8"))
    )
    (comp (ref "H4")
      (value "MOUNT-HOLE2.8")
      (footprint "eagle-import:2,8")
      (libsource (lib "eagle-import") (part "MOUNT-HOLE2.8"))
    )
    (comp (ref "H5")
      (value "MOUNT-HOLE2.8")
      (footprint "eagle-import:2,8")
      (libsource (lib "eagle-import") (part "MOUNT-HOLE2.8"))
    )
    (comp (ref "H6")
      (value "MOUNT-HOLE2.8")
      (footprint "eagle-import:2,8")
      (libsource (lib "eagle-import") (part "MOUNT-HOLE2.8"))
    )
    (comp (ref "IC17")
      (value "L78MXXAB")
      (footprint "eagle-import:D-PAK_TO252AA")
      (libsource (lib "eagle-import") (part "L78MXXAB"))
    )
    (comp (ref "IC18")
      (value "LM1117")
      (footprint "eagle-import:SOT223")
      (libsource (lib "eagle-import") (part "LM1117"))
    )
    (comp (ref "IC19")
      (value "MC34063AD")
      (footprint "eagle-import:SOIC8")
      (libsource (lib "eagle-import") (part "MC34063AD"))
    )
    (comp (ref "JP1")
      (value "PINHD-2X3")
      (footprint "eagle-import:2X03")
      (libsource (lib "eagle-import") (part "PINHD-2X3"))
    )
    (comp (ref "L1")
      (value "SDR0805")
      (footprint "eagle-import:SDR0805")
      (libsource (lib "eagle-import") (part "SDR0805"))
    )
    (comp (ref "LD2")
      (value "LEDCHIPLED_0805")
      (footprint "eagle-import:CHIPLED_0805")
      (libsource (lib "eagle-import") (part "LEDCHIPLED_0805"))
    )
    (comp (ref "LD3")
      (value "LEDCHIPLED_0805")
      (footprint "eagle-import:CHIPLED_0805")
      (libsource (lib "eagle-import") (part "LEDCHIPLED_0805"))
    )
    (comp (ref "P1")
      (value "B3B-EH-A")
      (footprint "eagle-import:B3B-EH-A")
      (libsource (lib "eagle-import") (part "B3B-EH-A"))
    )
    (comp (ref "P2")
      (value "B3B-EH-A")
      (footprint "eagle-import:B3B-EH-A")
      (libsource (lib "eagle-import") (part "B3B-EH-A"))
    )
    (comp (ref "P3")
      (value "B3B-EH-A")
      (footprint "eagle-import:B3B-EH-A")
      (libsource (lib "eagle-import") (part "B3B-EH-A"))
    )
    (comp (ref "P4")
      (value "B3B-EH-A")
      (footprint "eagle-import:B3B-EH-A")
      (libsource (lib "eagle-import") (part "B3B-EH-A"))
    )
    (comp (ref "P5")
      (value "B3B-EH-A")
      (footprint "eagle-import:B3B-EH-A")
      (libsource (lib "eagle-import") (part "B3B-EH-A"))
    )
    (comp (ref "P6")
      (value "B3B-EH-A")
      (footprint "eagle-import:B3B-EH-A")
      (libsource (lib "eagle-import") (part "B3B-EH-A"))
    )
    (comp (ref "R82")
      (value "R-EU_M0805")
      (footprint "eagle-import:M0805")
      (libsource (lib "eagle-import") (part "R-EU_M0805"))
    )
    (comp (ref "R83")
      (value "R-EU_M0805")
      (footprint "eagle-import:M0805")
      (libsource (lib "eagle-import") (part "R-EU_M0805"))
    )
    (comp (ref "R84")
      (value "0.2")
      (footprint "eagle-import:R2512")
      (libsource (lib "eagle-import") (part "R-EU_R2512"))
    )
    (comp (ref "R85")
      (value "1.2k")
      (footprint "eagle-import:M0805")
      (libsource (lib "eagle-import") (part "R-EU_M0805"))
    )
    (comp (ref "R86")
      (value "13.2k")
      (footprint "eagle-import:M0805")
      (libsource (lib "eagle-import") (part "R-EU_M0805"))
    )
    (comp (ref "U$1")
      (value "MC33269DPAK")
      (footprint "eagle-import:D-PAK_TO252AA")
      (libsource (lib "eagle-import") (part "MC33269DPAK"))
    )
    (comp (ref "C1")
      (value "220uF 25v")
      (footprint "eagle-import:140CLH-1010")
      (libsource (lib "eagle-import") (part "resistor_CPOL-EU140CLH-1010"))
    )
    (comp (ref "C2")
      (value "C-EUC0603")
      (footprint "eagle-import:C0603")
      (libsource (lib "eagle-import") (part "resistor_C-EUC0603"))
    )
    (comp (ref "C3")
      (value "C-EU150-091X182")
      (footprint "eagle-import:C150-091X182")
      (libsource (lib "eagle-import") (part "C-EU150-091X182"))
    )
    (comp (ref "C4")
      (value "10uF 50v")
      (footprint "eagle-import:C1210K")
      (libsource (lib "eagle-import") (part "resistor_C-EUC1210K"))
    )
    (comp (ref "C5")
      (value "10uF 50v")
      (footprint "eagle-import:C1210K")
      (libsource (lib "eagle-import") (part "resistor_C-EUC1210K"))
    )
    (comp (ref "C6")
      (value "10uF 50v")
      (footprint "eagle-import:C1210K")
      (libsource (lib "eagle-import") (part "resistor_C-EUC1210K"))
    )
    (comp (ref "C8")
      (value "0.1uF")
      (footprint "eagle-import:C0805")
      (libsource (lib "eagle-import") (part "resistor_C-EUC0805"))
    )
    (comp (ref "C10")
      (value "C-EUC0603")
      (footprint "eagle-import:C0603")
      (libsource (lib "eagle-import") (part "resistor_C-EUC0603"))
    )
    (comp (ref "C11")
      (value "C-EUC0603")
      (footprint "eagle-import:C0603")
      (libsource (lib "eagle-import") (part "resistor_C-EUC0603"))
    )
    (comp (ref "C14")
      (value "0.1uF")
      (footprint "eagle-import:C0805")
      (libsource (lib "eagle-import") (part "resistor_C-EUC0805"))
    )
    (comp (ref "C15")
      (value "0.1uF")
      (footprint "eagle-import:C0805")
      (libsource (lib "eagle-import") (part "resistor_C-EUC0805"))
    )
    (comp (ref "C20")
      (value "C-EUC0603")
      (footprint "eagle-import:C0603")
      (libsource (lib "eagle-import") (part "resistor_C-EUC0603"))
    )
    (comp (ref "C22")
      (value "C-EUC0603")
      (footprint "eagle-import:C0603")
      (libsource (lib "eagle-import") (part "resistor_C-EUC0603"))
    )
    (comp (ref "C23")
      (value "C-EUC0603")
      (footprint "eagle-import:C0603")
      (libsource (lib "eagle-import") (part "resistor_C-EUC0603"))
    )
    (comp (ref "D1")
      (value "SUPPRESSOR-SMBJ")
      (footprint "eagle-import:SMBJ")
      (libsource (lib "eagle-import") (part "SUPPRESSOR-SMBJ"))
    )
    (comp (ref "D5")
      (value "BAS70")
      (footprint "eagle-import:SOT23")
      (libsource (lib "eagle-import") (part "BAS70"))
    )
    (comp (ref "D6")
      (value "BAS70")
      (footprint "eagle-import:SOT23")
      (libsource (lib "eagle-import") (part "BAS70"))
    )
    (comp (ref "D7")
      (value "BAS70")
      (footprint "eagle-import:SOT23")
      (libsource (lib "eagle-import") (part "BAS70"))
    )
    (comp (ref "D8")
      (value "DIODE-MELF-MLL41")
      (footprint "eagle-import:MELF-MLL41")
      (libsource (lib "eagle-import") (part "DIODE-MELF-MLL41"))
    )
    (comp (ref "D9")
      (value "DIODE-MELF-MLL41")
      (footprint "eagle-import:MELF-MLL41")
      (libsource (lib "eagle-import") (part "DIODE-MELF-MLL41"))
    )
    (comp (ref "D10")
      (value "DIODE-MELF-MLL41")
      (footprint "eagle-import:MELF-MLL41")
      (libsource (lib "eagle-import") (part "DIODE-MELF-MLL41"))
    )
    (comp (ref "IC1")
      (value "FSBB30CH60")
      (footprint "eagle-import:FSBB30CH60")
      (fields (field (name "MPN") "FSBB30CH60B"))
      (libsource (lib "eagle-import") (part "FSBB30CH60"))
    )
    (comp (ref "J1")
      (value "0480251190")
      (footprint "eagle-import:JACK")
      (fields
        (field (name "DIGIKEY_PART_NUMBER") "WM5484-ND")
        (field (name "MANUFACTURER") "Molex")
        (field (name "CREATED_BY") "PCBLayout.com")
      )
      (libsource (lib "eagle-import") (part "0480251190"))
    )
    (comp (ref "R1")
      (value "R-EU_R0603")
      (footprint "eagle-import:R0603")
      (libsource (lib "eagle-import") (part "resistor_R-EU_R0603"))
    )
    (comp (ref "R2")
      (value "R-EU_R0603")
      (footprint "eagle-import:R0603")
      (libsource (lib "eagle-import") (part "resistor_R-EU_R0603"))
    )
    (comp (ref "R4")
      (value "0.1R")
      (footprint "eagle-import:R2512")
      (libsource (lib "eagle-import") (part "resistor_R-EU_R2512"))
    )
    (comp (ref "R5")
      (value "0.1R")
      (footprint "eagle-import:R2512")
      (libsource (lib "eagle-import") (part "resistor_R-EU_R2512"))
    )
    (comp (ref "R6")
      (value "0.1R")
      (footprint "eagle-import:R2512")
      (libsource (lib "eagle-import") (part "resistor_R-EU_R2512"))
    )
    (comp (ref "R7")
      (value "0.1R")
      (footprint "eagle-import:R2512")
      (libsource (lib "eagle-import") (part "resistor_R-EU_R2512"))
    )
    (comp (ref "R8")
      (value "0.1R")
      (footprint "eagle-import:R2512")
      (libsource (lib "eagle-import") (part "resistor_R-EU_R2512"))
    )
    (comp (ref "R9")
      (value "0.1R")
      (footprint "eagle-import:R2512")
      (libsource (lib "eagle-import") (part "resistor_R-EU_R2512"))
    )
    (comp (ref "R10")
      (value "R-EU_R1206")
      (footprint "eagle-import:R1206")
      (libsource (lib "eagle-import") (part "resistor_R-EU_R1206"))
    )
    (comp (ref "R11")
      (value "R-EU_R1206")
      (footprint "eagle-import:R1206")
      (libsource (lib "eagle-import") (part "resistor_R-EU_R1206"))
    )
    (comp (ref "R12")
      (value "R-EU_R1206")
      (footprint "eagle-import:R1206")
      (libsource (lib "eagle-import") (part "resistor_R-EU_R1206"))
    )
    (comp (ref "R17")
      (value "R-EU_R0603")
      (footprint "eagle-import:R0603")
      (libsource (lib "eagle-import") (part "resistor_R-EU_R0603"))
    )
    (comp (ref "R18")
      (value "R-EU_R0603")
      (footprint "eagle-import:R0603")
      (libsource (lib "eagle-import") (part "resistor_R-EU_R0603"))
    )
    (comp (ref "R19")
      (value "R-EU_R0603")
      (footprint "eagle-import:R0603")
      (libsource (lib "eagle-import") (part "resistor_R-EU_R0603"))
    )
    (comp (ref "X1")
      (value "DG129-7.5-02P")
      (footprint "eagle-import:DG129-7.5-02P-14-00A")
      (libsource (lib "eagle-import") (part "DG129-7.5-02P"))
    )
    (comp (ref "X3")
      (value "DG129-7.5-03P")
      (footprint "eagle-import:DG129-7.5-03P-14-00A")
      (libsource (lib "eagle-import") (part "DG129-7.5-03P"))
    )
    (comp (ref "C25")
      (value "C-EUC0603")
      (footprint "eagle-import:C0603")
      (libsource (lib "eagle-import") (part "resistor_C-EUC0603"))
    )
    (comp (ref "C47")
      (value "0.1uF")
      (footprint "eagle-import:C1206")
      (libsource (lib "eagle-import") (part "resistor_C-EUC1206"))
    )
    (comp (ref "C49")
      (value "0.1uF")
      (footprint "eagle-import:C1206")
      (libsource (lib "eagle-import") (part "resistor_C-EUC1206"))
    )
    (comp (ref "D2")
      (value "RS1J")
      (footprint "eagle-import:DIOM5326X292N")
      (libsource (lib "eagle-import") (part "SCHOTTKY_SMA"))
    )
    (comp (ref "D3")
      (value "GS3J")
      (footprint "eagle-import:DIOM7959X265N")
      (libsource (lib "eagle-import") (part "SCHOTTKY_SMC"))
    )
    (comp (ref "D11")
      (value "SCHOTTKY_SMA")
      (footprint "eagle-import:DIOM5326X292N")
      (libsource (lib "eagle-import") (part "SCHOTTKY_SMA"))
    )
    (comp (ref "IC13")
      (value "HCPL-3180-300E")
      (footprint "eagle-import:HCPL-3180")
      (fields
        (field (name "MOUSER_PART_NUMBER") "630-HCPL-3180-300E")
        (field (name "RS_PART_NUMBER") "8188347P")
      )
      (libsource (lib "eagle-import") (part "HCPL-3180-300E"))
    )
    (comp (ref "IC14")
      (value "HCPL-3180-300E")
      (footprint "eagle-import:HCPL-3180")
      (fields
        (field (name "MOUSER_PART_NUMBER") "630-HCPL-3180-300E")
        (field (name "RS_PART_NUMBER") "8188347P")
      )
      (libsource (lib "eagle-import") (part "HCPL-3180-300E"))
    )
    (comp (ref "IC15")
      (value "74AC14D")
      (footprint "eagle-import:SO14")
      (libsource (lib "eagle-import") (part "7414DAC"))
    )
    (comp (ref "K3")
      (value "HJR-21FF")
      (footprint "eagle-import:HJR21FF")
      (libsource (lib "eagle-import") (part "HJR-21FF"))
    )
    (comp (ref "Q2")
      (value "IRFP240-H")
      (footprint "eagle-import:TO247BH")
      (libsource (lib "eagle-import") (part "IRFP240-H"))
    )
    (comp (ref "Q3")
      (value "BC817-40SMD")
      (footprint "eagle-import:SOT23-BEC")
      (libsource (lib "eagle-import") (part "BC817SMD-40"))
    )
    (comp (ref "R15")
      (value "R-EU_R0603")
      (footprint "eagle-import:R0603")
      (libsource (lib "eagle-import") (part "resistor_R-EU_R0603"))
    )
    (comp (ref "R16")
      (value "R-EU_R0603")
      (footprint "eagle-import:R0603")
      (libsource (lib "eagle-import") (part "resistor_R-EU_R0603"))
    )
    (comp (ref "R65")
      (value "1k")
      (footprint "eagle-import:M0805")
      (libsource (lib "eagle-import") (part "resistor_R-EU_M0805"))
    )
    (comp (ref "R66")
      (value "1k")
      (footprint "eagle-import:M0805")
      (libsource (lib "eagle-import") (part "resistor_R-EU_M0805"))
    )
    (comp (ref "R67")
      (value "R-EU_M0805")
      (footprint "eagle-import:M0805")
      (libsource (lib "eagle-import") (part "resistor_R-EU_M0805"))
    )
    (comp (ref "R68")
      (value "R-EU_M0805")
      (footprint "eagle-import:M0805")
      (libsource (lib "eagle-import") (part "resistor_R-EU_M0805"))
    )
    (comp (ref "R69")
      (value "R-EU_M0805")
      (footprint "eagle-import:M0805")
      (libsource (lib "eagle-import") (part "resistor_R-EU_M0805"))
    )
    (comp (ref "R73")
      (value "R-EU_M0805")
      (footprint "eagle-import:M0805")
      (libsource (lib "eagle-import") (part "resistor_R-EU_M0805"))
    )
    (comp (ref "R75")
      (value "R-EU_M0805")
      (footprint "eagle-import:M0805")
      (libsource (lib "eagle-import") (part "resistor_R-EU_M0805"))
    )
    (comp (ref "X2")
      (value "DG129-7.5-02P")
      (footprint "eagle-import:DG129-7.5-02P-14-00A")
      (libsource (lib "eagle-import") (part "DG129-7.5-02P"))
    )
    (comp (ref "X4")
      (value "DG129-7.5-02P")
      (footprint "eagle-import:DG129-7.5-02P-14-00A")
      (libsource (lib "eagle-import") (part "DG129-7.5-02P"))
    )
  )
  (nets
    (net (code "1") (name "+3V3D") (class "Default")
      (node (ref "C59") (pin "1") (pinfunction "1_1") (pintype "passive"))
      (node (ref "C60") (pin "+") (pinfunction "+_+") (pintype "passive"))
      (node (ref "IC18") (pin "2") (pinfunction "OUTA_2") (pintype "bidirectional"))
      (node (ref "IC18") (pin "4") (pinfunction "OUTB_4") (pintype "bidirectional"))
      (node (ref "JP1") (pin "2") (pinfunction "2_2") (pintype "passive"))
      (node (ref "P5") (pin "1") (pinfunction "1_1") (pintype "passive"))
    )
    (net (code "2") (name "+5V") (class "Default")
      (node (ref "C65") (pin "1") (pinfunction "1_1") (pintype "passive"))
      (node (ref "C66") (pin "+") (pinfunction "+_+") (pintype "passive"))
      (node (ref "P4") (pin "1") (pinfunction "1_1") (pintype "passive"))
      (node (ref "U$1") (pin "4") (pinfunction "OUT_4") (pintype "bidirectional"))
    )
    (net (code "3") (name "+5VA") (class "Default")
      (node (ref "C21") (pin "1") (pinfunction "1_1") (pintype "passive"))
      (node (ref "C25") (pin "1") (pinfunction "1_1") (pintype "passive"))
      (node (ref "C29") (pin "1") (pinfunction "1_1") (pintype "passive"))
      (node (ref "C45") (pin "1") (pinfunction "1_1") (pintype "passive"))
      (node (ref "C54") (pin "1") (pinfunction "1_1") (pintype "passive"))
      (node (ref "C7") (pin "2") (pinfunction "2_2") (pintype "passive"))
      (node (ref "C73") (pin "1") (pinfunction "1_1") (pintype "passive"))
      (node (ref "IC15") (pin "14") (pinfunction "VCC_14") (pintype "power_in"))
      (node (ref "IC17") (pin "3") (pinfunction "OUT_3") (pintype "bidirectional"))
      (node (ref "IC2") (pin "1") (pinfunction "VDD_1") (pintype "power_in"))
      (node (ref "IC4") (pin "8") (pinfunction "V+_8") (pintype "power_in"))
      (node (ref "IC7") (pin "3") (pinfunction "C3_3") (pintype "passive"))
      (node (ref "IC8") (pin "3") (pinfunction "C3_3") (pintype "passive"))
      (node (ref "IC9") (pin "3") (pinfunction "C3_3") (pintype "passive"))
      (node (ref "OK1") (pin "8") (pinfunction "VCC_8") (pintype "passive"))
      (node (ref "OK2") (pin "8") (pinfunction "VCC_8") (pintype "passive"))
      (node (ref "OK3") (pin "8") (pinfunction "VCC_8") (pintype "passive"))
      (node (ref "OK4") (pin "1") (pinfunction "A1_1") (pintype "passive"))
      (node (ref "R100") (pin "2") (pinfunction "2_2") (pintype "passive"))
      (node (ref "R22") (pin "2") (pinfunction "2_2") (pintype "passive"))
      (node (ref "R24") (pin "2") (pinfunction "2_2") (pintype "passive"))
      (node (ref "R26") (pin "2") (pinfunction "2_2") (pintype "passive"))
      (node (ref "R36") (pin "2") (pinfunction "2_2") (pintype "passive"))
      (node (ref "R38") (pin "2") (pinfunction "2_2") (pintype "passive"))
      (node (ref "R39") (pin "2") (pinfunction "2_2") (pintype "passive"))
      (node (ref "R91") (pin "1") (pinfunction "1_1") (pintype "passive"))
      (node (ref "R94") (pin "1") (pinfunction "1_1") (pintype "passive"))
      (node (ref "R99") (pin "2") (pinfunction "2_2") (pintype "passive"))
    )
    (net (code "4") (name "+9V") (class "Default")
      (node (ref "C57") (pin "1") (pinfunction "1_1") (pintype "passive"))
      (node (ref "D15") (pin "A") (pinfunction "A_A") (pintype "passive"))
      (node (ref "P6") (pin "1") (pinfunction "1_1") (pintype "passive"))
    )
    (net (code "5") (name "+15V") (class "Default")
      (node (ref "C1") (pin "+") (pinfunction "+_+") (pintype "passive"))
      (node (ref "C10") (pin "1") (pinfunction "1_1") (pintype "passive"))
      (node (ref "C47") (pin "1") (pinfunction "1_1") (pintype "passive"))
      (node (ref "C49") (pin "1") (pinfunction "1_1") (pintype "passive"))
      (node (ref "C56") (pin "1") (pinfunction "1_1") (pintype "passive"))
      (node (ref "C63") (pin "+") (pinfunction "+_+") (pintype "passive"))
      (node (ref "D1") (pin "C") (pinfunction "C_C") (pintype "passive"))
      (node (ref "IC1") (pin "1") (pinfunction "VCCL_1") (pintype "power_in"))
      (node (ref "IC1") (pin "10") (pinfunction "VCCUH_10") (pintype "input"))
      (node (ref "IC1") (pin "14") (pinfunction "VCCVH_14") (pintype "input"))
      (node (ref "IC1") (pin "18") (pinfunction "VCCWH_18") (pintype "input"))
      (node (ref "IC13") (pin "5") (pinfunction "VEE_5") (pintype "bidirectional"))
      (node (ref "IC14") (pin "5") (pinfunction "VEE_5") (pintype "bidirectional"))
      (node (ref "IC17") (pin "1") (pinfunction "IN_1") (pintype "bidirectional"))
      (node (ref "L1") (pin "2") (pinfunction "2_2") (pintype "passive"))
      (node (ref "P3") (pin "1") (pinfunction "1_1") (pintype "passive"))
      (node (ref "R10") (pin "1") (pinfunction "1_1") (pintype "passive"))
      (node (ref "R11") (pin "1") (pinfunction "1_1") (pintype "passive"))
      (node (ref "R12") (pin "1") (pinfunction "1_1") (pintype "passive"))
      (node (ref "R65") (pin "2") (pinfunction "2_2") (pintype "passive"))
      (node (ref "R66") (pin "2") (pinfunction "2_2") (pintype "passive"))
      (node (ref "R75") (pin "2") (pinfunction "2_2") (pintype "passive"))
      (node (ref "R86") (pin "1") (pinfunction "1_1") (pintype "passive"))
    )
    (net (code "6") (name "+24V") (class "Default")
      (node (ref "C55") (pin "1") (pinfunction "1_1") (pintype "passive"))
      (node (ref "D13") (pin "A") (pinfunction "A_A") (pintype "passive"))
      (node (ref "P1") (pin "1") (pinfunction "1_1") (pintype "passive"))
      (node (ref "P2") (pin "1") (pinfunction "1_1") (pintype "passive"))
    )
    (net (code "7") (name "1V65") (class "Default")
      (node (ref "C31") (pin "+") (pinfunction "+_+") (pintype "passive"))
      (node (ref "IC4") (pin "6") (pinfunction "-IN_6") (pintype "input"))
      (node (ref "IC4") (pin "7") (pinfunction "OUT_7") (pintype "output"))
      (node (ref "R37") (pin "2") (pinfunction "2_2") (pintype "passive"))
      (node (ref "R79") (pin "2") (pinfunction "2_2") (pintype "passive"))
      (node (ref "R97") (pin "2") (pinfunction "2_2") (pintype "passive"))
    )
    (net (code "8") (name "3.3V") (class "Default")
      (node (ref "C43") (pin "1") (pinfunction "1_1") (pintype "passive"))
      (node (ref "IC5") (pin "8") (pinfunction "V+_8") (pintype "power_in"))
      (node (ref "IC6") (pin "8") (pinfunction "V+_8") (pintype "power_in"))
      (node (ref "R59") (pin "2") (pinfunction "2_2") (pintype "passive"))
    )
    (net (code "9") (name "AGND") (class "Default")
      (node (ref "C1") (pin "-") (pinfunction "-_-") (pintype "passive"))
      (node (ref "C10") (pin "2") (pinfunction "2_2") (pintype "passive"))
      (node (ref "C11") (pin "1") (pinfunction "1_1") (pintype "passive"))
      (node (ref "C12") (pin "-") (pinfunction "-_-") (pintype "passive"))
      (node (ref "C13") (pin "2") (pinfunction "2_2") (pintype "passive"))
      (node (ref "C16") (pin "2") (pinfunction "2_2") (pintype "passive"))
      (node (ref "C17") (pin "2") (pinfunction "2_2") (pintype "passive"))
      (node (ref "C18") (pin "2") (pinfunction "2_2") (pintype "passive"))
      (node (ref "C19") (pin "2") (pinfunction "2_2") (pintype "passive"))
      (node (ref "C2") (pin "2") (pinfunction "2_2") (pintype "passive"))
      (node (ref "C20") (pin "2") (pinfunction "2_2") (pintype "passive"))
      (node (ref "C21") (pin "2") (pinfunction "2_2") (pintype "passive"))
      (node (ref "C22") (pin "2") (pinfunction "2_2") (pintype "passive"))
      (node (ref "C23") (pin "2") (pinfunction "2_2") (pintype "passive"))
      (node (ref "C24") (pin "-") (pinfunction "-_-") (pintype "passive"))
      (node (ref "C25") (pin "2") (pinfunction "2_2") (pintype "passive"))
      (node (ref "C29") (pin "2") (pinfunction "2_2") (pintype "passive"))
      (node (ref "C3") (pin "2") (pinfunction "2_2") (pintype "passive"))
      (node (ref "C30") (pin "2") (pinfunction "2_2") (pintype "passive"))
      (node (ref "C31") (pin "-") (pinfunction "-_-") (pintype "passive"))
      (node (ref "C33") (pin "1") (pinfunction "1_1") (pintype "passive"))
      (node (ref "C35") (pin "-") (pinfunction "-_-") (pintype "passive"))
      (node (ref "C37") (pin "-") (pinfunction "-_-") (pintype "passive"))
      (node (ref "C39") (pin "2") (pinfunction "2_2") (pintype "passive"))
      (node (ref "C40") (pin "2") (pinfunction "2_2") (pintype "passive"))
      (node (ref "C44") (pin "2") (pinfunction "2_2") (pintype "passive"))
      (node (ref "C45") (pin "2") (pinfunction "2_2") (pintype "passive"))
      (node (ref "C46") (pin "2") (pinfunction "2_2") (pintype "passive"))
      (node (ref "C47") (pin "2") (pinfunction "2_2") (pintype "passive"))
      (node (ref "C49") (pin "2") (pinfunction "2_2") (pintype "passive"))
      (node (ref "C53") (pin "2") (pinfunction "2_2") (pintype "passive"))
      (node (ref "C54") (pin "2") (pinfunction "2_2") (pintype "passive"))
      (node (ref "C55") (pin "2") (pinfunction "2_2") (pintype "passive"))
      (node (ref "C56") (pin "2") (pinfunction "2_2") (pintype "passive"))
      (node (ref "C63") (pin "-") (pinfunction "-_-") (pintype "passive"))
      (node (ref "C7") (pin "1") (pinfunction "1_1") (pintype "passive"))
      (node (ref "C72") (pin "2") (pinfunction "2_2") (pintype "passive"))
      (node (ref "C73") (pin "2") (pinfunction "2_2") (pintype "passive"))
      (node (ref "C74") (pin "2") (pinfunction "2_2") (pintype "passive"))
      (node (ref "C75") (pin "2") (pinfunction "2_2") (pintype "passive"))
      (node (ref "C9") (pin "2") (pinfunction "2_2") (pintype "passive"))
      (node (ref "D1") (pin "A") (pinfunction "A_A") (pintype "passive"))
      (node (ref "D14") (pin "A") (pinfunction "A_A") (pintype "passive"))
      (node (ref "IC1") (pin "2") (pinfunction "COM_2") (pintype "power_in"))
      (node (ref "IC10") (pin "4") (pinfunction "V-_4") (pintype "power_in"))
      (node (ref "IC12") (pin "1") (pinfunction "C1_1") (pintype "passive"))
      (node (ref "IC13") (pin "8") (pinfunction "VCC_8") (pintype "bidirectional"))
      (node (ref "IC14") (pin "8") (pinfunction "VCC_8") (pintype "bidirectional"))
      (node (ref "IC15") (pin "7") (pinfunction "GND_7") (pintype "power_in"))
      (node (ref "IC17") (pin "4") (pinfunction "GND_4") (pintype "bidirectional"))
      (node (ref "IC19") (pin "4") (pinfunction "GND_4") (pintype "passive"))
      (node (ref "IC2") (pin "8") (pinfunction "VSS_8") (pintype "power_in"))
      (node (ref "IC3") (pin "4") (pinfunction "V-_4") (pintype "power_in"))
      (node (ref "IC4") (pin "4") (pinfunction "V-_4") (pintype "power_in"))
      (node (ref "IC7") (pin "1") (pinfunction "C1_1") (pintype "passive"))
      (node (ref "IC8") (pin "1") (pinfunction "C1_1") (pintype "passive"))
      (node (ref "IC9") (pin "1") (pinfunction "C1_1") (pintype "passive"))
      (node (ref "OK1") (pin "5") (pinfunction "GND_5") (pintype "passive"))
      (node (ref "OK2") (pin "5") (pinfunction "GND_5") (pintype "passive"))
      (node (ref "OK3") (pin "5") (pinfunction "GND_5") (pintype "passive"))
      (node (ref "P1") (pin "3") (pinfunction "3_3") (pintype "passive"))
      (node (ref "P2") (pin "3") (pinfunction "3_3") (pintype "passive"))
      (node (ref "P3") (pin "3") (pinfunction "3_3") (pintype "passive"))
      (node (ref "Q1") (pin "E") (pinfunction "E_E") (pintype "passive"))
      (node (ref "Q2") (pin "S") (pinfunction "S_S") (pintype "passive"))
      (node (ref "Q3") (pin "E") (pinfunction "E_E") (pintype "passive"))
      (node (ref "R1") (pin "1") (pinfunction "1_1") (pintype "passive"))
      (node (ref "R101") (pin "1") (pinfunction "1_1") (pintype "passive"))
      (node (ref "R33") (pin "2") (pinfunction "2_2") (pintype "passive"))
      (node (ref "R4") (pin "2") (pinfunction "2_2") (pintype "passive"))
      (node (ref "R5") (pin "2") (pinfunction "2_2") (pintype "passive"))
      (node (ref "R52") (pin "2") (pinfunction "2_2") (pintype "passive"))
      (node (ref "R54") (pin "2") (pinfunction "2_2") (pintype "passive"))
      (node (ref "R6") (pin "2") (pinfunction "2_2") (pintype "passive"))
      (node (ref "R7") (pin "2") (pinfunction "2_2") (pintype "passive"))
      (node (ref "R8") (pin "2") (pinfunction "2_2") (pintype "passive"))
      (node (ref "R82") (pin "1") (pinfunction "1_1") (pintype "passive"))
      (node (ref "R85") (pin "1") (pinfunction "1_1") (pintype "passive"))
      (node (ref "R87") (pin "2") (pinfunction "2_2") (pintype "passive"))
      (node (ref "R9") (pin "2") (pinfunction "2_2") (pintype "passive"))
      (node (ref "R93") (pin "2") (pinfunction "2_2") (pintype "passive"))
      (node (ref "R95") (pin "2") (pinfunction "2_2") (pintype "passive"))
      (node (ref "X1") (pin "1") (pinfunction "1_1") (pintype "passive"))
    )
    (net (code "10") (name "BR_CON") (class "Default")
      (node (ref "R16") (pin "1") (pinfunction "1_1") (pintype "passive"))
      (node (ref "SV1") (pin "12") (pinfunction "12_12") (pintype "passive"))
    )
    (net (code "11") (name "DGND") (class "Default")
      (node (ref "C36") (pin "2") (pinfunction "2_2") (pintype "passive"))
      (node (ref "C42") (pin "2") (pinfunction "2_2") (pintype "passive"))
      (node (ref "C43") (pin "2") (pinfunction "2_2") (pintype "passive"))
      (node (ref "C48") (pin "2") (pinfunction "2_2") (pintype "passive"))
      (node (ref "C57") (pin "2") (pinfunction "2_2") (pintype "passive"))
      (node (ref "C58") (pin "2") (pinfunction "2_2") (pintype "passive"))
      (node (ref "C59") (pin "2") (pinfunction "2_2") (pintype "passive"))
      (node (ref "C60") (pin "-") (pinfunction "-_-") (pintype "passive"))
      (node (ref "C62") (pin "1") (pinfunction "1_1") (pintype "passive"))
      (node (ref "C64") (pin "2") (pinfunction "2_2") (pintype "passive"))
      (node (ref "C65") (pin "2") (pinfunction "2_2") (pintype "passive"))
      (node (ref "C66") (pin "-") (pinfunction "-_-") (pintype "passive"))
      (node (ref "C70") (pin "1") (pinfunction "1_1") (pintype "passive"))
      (node (ref "C71") (pin "2") (pinfunction "2_2") (pintype "passive"))
      (node (ref "D16") (pin "2") (pinfunction "C_2") (pintype "passive"))
      (node (ref "IC11") (pin "3") (pinfunction "+IN_3") (pintype "input"))
      (node (ref "IC11") (pin "4") (pinfunction "V-_4") (pintype "power_in"))
      (node (ref "IC11") (pin "5") (pinfunction "+IN_5") (pintype "input"))
      (node (ref "IC12") (pin "5") (pinfunction "A5_5") (pintype "passive"))
      (node (ref "IC13") (pin "1") (pinfunction "NC_1_1") (pintype "bidirectional"))
      (node (ref "IC13") (pin "3") (pinfunction "CATHODE_3") (pintype "bidirectional"))
      (node (ref "IC13") (pin "4") (pinfunction "NC_2_4") (pintype "bidirectional"))
      (node (ref "IC14") (pin "1") (pinfunction "NC_1_1") (pintype "bidirectional"))
      (node (ref "IC14") (pin "3") (pinfunction "CATHODE_3") (pintype "bidirectional"))
      (node (ref "IC14") (pin "4") (pinfunction "NC_2_4") (pintype "bidirectional"))
      (node (ref "IC18") (pin "1") (pinfunction "GND_1") (pintype "bidirectional"))
      (node (ref "IC5") (pin "3") (pinfunction "+IN_3") (pintype "input"))
      (node (ref "IC5") (pin "4") (pinfunction "V-_4") (pintype "power_in"))
      (node (ref "IC5") (pin "5") (pinfunction "+IN_5") (pintype "input"))
      (node (ref "IC6") (pin "2") (pinfunction "-IN_2") (pintype "input"))
      (node (ref "IC6") (pin "4") (pinfunction "V-_4") (pintype "power_in"))
      (node (ref "IC6") (pin "5") (pinfunction "+IN_5") (pintype "input"))
      (node (ref "IC7") (pin "5") (pinfunction "A5_5") (pintype "passive"))
      (node (ref "IC8") (pin "5") (pinfunction "A5_5") (pintype "passive"))
      (node (ref "IC9") (pin "5") (pinfunction "A5_5") (pintype "passive"))
      (node (ref "OK4") (pin "5") (pinfunction "GND_5") (pintype "passive"))
      (node (ref "P4") (pin "3") (pinfunction "3_3") (pintype "passive"))
      (node (ref "P5") (pin "3") (pinfunction "3_3") (pintype "passive"))
      (node (ref "P6") (pin "3") (pinfunction "3_3") (pintype "passive"))
      (node (ref "R78") (pin "1") (pinfunction "1_1") (pintype "passive"))
      (node (ref "R83") (pin "1") (pinfunction "1_1") (pintype "passive"))
      (node (ref "SV1") (pin "1") (pinfunction "1_1") (pintype "passive"))
      (node (ref "SV1") (pin "10") (pinfunction "10_10") (pintype "passive"))
      (node (ref "SV1") (pin "15") (pinfunction "15_15") (pintype "passive"))
      (node (ref "SV1") (pin "20") (pinfunction "20_20") (pintype "passive"))
      (node (ref "SV1") (pin "9") (pinfunction "9_9") (pintype "passive"))
      (node (ref "U$1") (pin "1") (pinfunction "GND_1") (pintype "bidirectional"))
      (node (ref "U$2") (pin "2") (pinfunction "GND_2") (pintype "power_in"))
    )
    (net (code "12") (name "EXT_VCC") (class "Default")
      (node (ref "JP1") (pin "6") (pinfunction "6_6") (pintype "passive"))
      (node (ref "SV1") (pin "2") (pinfunction "2_2") (pintype "passive"))
    )
    (net (code "13") (name "FLT") (class "Default")
      (node (ref "OK4") (pin "7") (pinfunction "VO1_7") (pintype "passive"))
      (node (ref "R30") (pin "2") (pinfunction "2_2") (pintype "passive"))
      (node (ref "SV1") (pin "11") (pinfunction "11_11") (pintype "passive"))
    )
    (net (code "14") (name "INUH") (class "Default")
      (node (ref "C9") (pin "1") (pinfunction "1_1") (pintype "passive"))
      (node (ref "IC1") (pin "9") (pinfunction "INUH_9") (pintype "input"))
      (node (ref "IC2") (pin "10") (pinfunction "O_10") (pintype "output"))
    )
    (net (code "15") (name "INUL") (class "Default")
      (node (ref "C13") (pin "1") (pinfunction "1_1") (pintype "passive"))
      (node (ref "IC1") (pin "3") (pinfunction "INUL_3") (pintype "input"))
      (node (ref "IC2") (pin "6") (pinfunction "O_6") (pintype "output"))
    )
    (net (code "16") (name "INVH") (class "Default")
      (node (ref "C16") (pin "1") (pinfunction "1_1") (pintype "passive"))
      (node (ref "IC1") (pin "13") (pinfunction "INVH_13") (pintype "input"))
      (node (ref "IC2") (pin "12") (pinfunction "O_12") (pintype "output"))
    )
    (net (code "17") (name "INVL") (class "Default")
      (node (ref "C17") (pin "1") (pinfunction "1_1") (pintype "passive"))
      (node (ref "IC1") (pin "4") (pinfunction "INVL_4") (pintype "input"))
      (node (ref "IC2") (pin "4") (pinfunction "O_4") (pintype "output"))
    )
    (net (code "18") (name "INWH") (class "Default")
      (node (ref "C18") (pin "1") (pinfunction "1_1") (pintype "passive"))
      (node (ref "IC1") (pin "17") (pinfunction "INWH_17") (pintype "input"))
      (node (ref "IC2") (pin "15") (pinfunction "O_15") (pintype "output"))
    )
    (net (code "19") (name "INWL") (class "Default")
      (node (ref "C19") (pin "1") (pinfunction "1_1") (pintype "passive"))
      (node (ref "IC1") (pin "5") (pinfunction "INWL_5") (pintype "input"))
      (node (ref "IC2") (pin "2") (pinfunction "O_2") (pintype "output"))
    )
    (net (code "20") (name "I_U") (class "Default")
      (node (ref "C23") (pin "1") (pinfunction "1_1") (pintype "passive"))
      (node (ref "D7") (pin "1") (pinfunction "A_1") (pintype "passive"))
      (node (ref "R19") (pin "1") (pinfunction "1_1") (pintype "passive"))
      (node (ref "R44") (pin "2") (pinfunction "2_2") (pintype "passive"))
    )
    (net (code "21") (name "I_U_OUT") (class "Default")
      (node (ref "C69") (pin "1") (pinfunction "1_1") (pintype "passive"))
      (node (ref "IC6") (pin "1") (pinfunction "OUT_1") (pintype "output"))
      (node (ref "R62") (pin "1") (pinfunction "1_1") (pintype "passive"))
      (node (ref "SV1") (pin "17") (pinfunction "17_17") (pintype "passive"))
    )
    (net (code "22") (name "I_V") (class "Default")
      (node (ref "C22") (pin "1") (pinfunction "1_1") (pintype "passive"))
      (node (ref "D6") (pin "1") (pinfunction "A_1") (pintype "passive"))
      (node (ref "R18") (pin "1") (pinfunction "1_1") (pintype "passive"))
      (node (ref "R81") (pin "2") (pinfunction "2_2") (pintype "passive"))
    )
    (net (code "23") (name "I_V_OUT") (class "Default")
      (node (ref "C67") (pin "1") (pinfunction "1_1") (pintype "passive"))
      (node (ref "IC5") (pin "7") (pinfunction "OUT_7") (pintype "output"))
      (node (ref "R61") (pin "1") (pinfunction "1_1") (pintype "passive"))
      (node (ref "SV1") (pin "19") (pinfunction "19_19") (pintype "passive"))
    )
    (net (code "24") (name "I_W") (class "Default")
      (node (ref "C20") (pin "1") (pinfunction "1_1") (pintype "passive"))
      (node (ref "D5") (pin "1") (pinfunction "A_1") (pintype "passive"))
      (node (ref "R17") (pin "1") (pinfunction "1_1") (pintype "passive"))
      (node (ref "R98") (pin "2") (pinfunction "2_2") (pintype "passive"))
    )
    (net (code "25") (name "I_W_OUT") (class "Default")
      (node (ref "C50") (pin "1") (pinfunction "1_1") (pintype "passive"))
      (node (ref "IC5") (pin "1") (pinfunction "OUT_1") (pintype "output"))
      (node (ref "R60") (pin "1") (pinfunction "1_1") (pintype "passive"))
      (node (ref "SV1") (pin "16") (pinfunction "16_16") (pintype "passive"))
    )
    (net (code "26") (name "Net-(C44-Pad1)") (class "Default")
      (node (ref "C44") (pin "1") (pinfunction "1_1") (pintype "passive"))
      (node (ref "R51") (pin "1") (pinfunction "1_1") (pintype "passive"))
      (node (ref "R52") (pin "1") (pinfunction "1_1") (pintype "passive"))
      (node (ref "R53") (pin "1") (pinfunction "1_1") (pintype "passive"))
    )
    (net (code "27") (name "Net-(D2-PadA)") (class "Default")
      (node (ref "D2") (pin "A") (pinfunction "A_A") (pintype "passive"))
      (node (ref "Q2") (pin "G") (pinfunction "G_G") (pintype "passive"))
      (node (ref "R67") (pin "1") (pinfunction "1_1") (pintype "passive"))
    )
    (net (code "28") (name "Net-(D2-PadK)") (class "Default")
      (node (ref "D2") (pin "K") (pinfunction "K_K") (pintype "passive"))
      (node (ref "R69") (pin "1") (pinfunction "1_1") (pintype "passive"))
    )
    (net (code "29") (name "Net-(D5-C)") (class "Default")
      (node (ref "D5") (pin "3") (pinfunction "C_3") (pintype "passive"))
      (node (ref "D6") (pin "3") (pinfunction "C_3") (pintype "passive"))
      (node (ref "D7") (pin "3") (pinfunction "C_3") (pintype "passive"))
      (node (ref "R2") (pin "1") (pinfunction "1_1") (pintype "passive"))
    )
    (net (code "30") (name "Net-(D8-PadA)") (class "Default")
      (node (ref "D8") (pin "A") (pinfunction "A_A") (pintype "passive"))
      (node (ref "R12") (pin "2") (pinfunction "2_2") (pintype "passive"))
    )
    (net (code "31") (name "Net-(D9-PadA)") (class "Default")
      (node (ref "D9") (pin "A") (pinfunction "A_A") (pintype "passive"))
      (node (ref "R11") (pin "2") (pinfunction "2_2") (pintype "passive"))
    )
    (net (code "32") (name "Net-(D10-PadA)") (class "Default")
      (node (ref "D10") (pin "A") (pinfunction "A_A") (pintype "passive"))
      (node (ref "R10") (pin "2") (pinfunction "2_2") (pintype "passive"))
    )
    (net (code "33") (name "Net-(D11-PadA)") (class "Default")
      (node (ref "D11") (pin "A") (pinfunction "A_A") (pintype "passive"))
      (node (ref "K3") (pin "COIL_2") (pinfunction "COIL_2_COIL_2") (pintype "passive"))
      (node (ref "Q3") (pin "C") (pinfunction "C_C") (pintype "passive"))
    )
    (net (code "34") (name "Net-(D11-PadK)") (class "Default")
      (node (ref "D11") (pin "K") (pinfunction "K_K") (pintype "passive"))
      (node (ref "K3") (pin "COIL_1") (pinfunction "COIL_1_COIL_1") (pintype "passive"))
      (node (ref "R73") (pin "1") (pinfunction "1_1") (pintype "passive"))
    )
    (net (code "35") (name "Net-(D16-A)") (class "Default")
      (node (ref "C41") (pin "2") (pinfunction "2_2") (pintype "passive"))
      (node (ref "C48") (pin "1") (pinfunction "1_1") (pintype "passive"))
      (node (ref "D16") (pin "1") (pinfunction "A_1") (pintype "passive"))
      (node (ref "R58") (pin "1") (pinfunction "1_1") (pintype "passive"))
      (node (ref "U$2") (pin "3") (pinfunction "IN-_3") (pintype "input"))
    )
    (net (code "36") (name "Net-(IC1-CFOD)") (class "Default")
      (node (ref "C11") (pin "2") (pinfunction "2_2") (pintype "passive"))
      (node (ref "IC1") (pin "7") (pinfunction "CFOD_7") (pintype "passive"))
    )
    (net (code "37") (name "Net-(IC1-CSC)") (class "Default")
      (node (ref "C2") (pin "1") (pinfunction "1_1") (pintype "passive"))
      (node (ref "IC1") (pin "8") (pinfunction "CSC_8") (pintype "passive"))
      (node (ref "R1") (pin "2") (pinfunction "2_2") (pintype "passive"))
      (node (ref "R2") (pin "2") (pinfunction "2_2") (pintype "passive"))
    )
    (net (code "38") (name "Net-(IC1-NU)") (class "Default")
      (node (ref "IC1") (pin "21") (pinfunction "NU_21") (pintype "input"))
      (node (ref "R19") (pin "2") (pinfunction "2_2") (pintype "passive"))
      (node (ref "R8") (pin "1") (pinfunction "1_1") (pintype "passive"))
      (node (ref "R9") (pin "1") (pinfunction "1_1") (pintype "passive"))
    )
    (net (code "39") (name "Net-(IC1-NV)") (class "Default")
      (node (ref "IC1") (pin "22") (pinfunction "NV_22") (pintype "input"))
      (node (ref "R18") (pin "2") (pinfunction "2_2") (pintype "passive"))
      (node (ref "R6") (pin "1") (pinfunction "1_1") (pintype "passive"))
      (node (ref "R7") (pin "1") (pinfunction "1_1") (pintype "passive"))
    )
    (net (code "40") (name "Net-(IC1-NW)") (class "Default")
      (node (ref "IC1") (pin "23") (pinfunction "NW_23") (pintype "input"))
      (node (ref "R17") (pin "2") (pinfunction "2_2") (pintype "passive"))
      (node (ref "R4") (pin "1") (pinfunction "1_1") (pintype "passive"))
      (node (ref "R5") (pin "1") (pinfunction "1_1") (pintype "passive"))
    )
    (net (code "41") (name "Net-(IC1-VBU)") (class "Default")
      (node (ref "C15") (pin "1") (pinfunction "1_1") (pintype "passive"))
      (node (ref "C6") (pin "1") (pinfunction "1_1") (pintype "passive"))
      (node (ref "D8") (pin "C") (pinfunction "C_C") (pintype "passive"))
      (node (ref "IC1") (pin "11") (pinfunction "VBU_11") (pintype "input"))
    )
    (net (code "42") (name "Net-(IC1-VBV)") (class "Default")
      (node (ref "C14") (pin "1") (pinfunction "1_1") (pintype "passive"))
      (node (ref "C5") (pin "1") (pinfunction "1_1") (pintype "passive"))
      (node (ref "D9") (pin "C") (pinfunction "C_C") (pintype "passive"))
      (node (ref "IC1") (pin "15") (pinfunction "VBV_15") (pintype "input"))
    )
    (net (code "43") (name "Net-(IC1-VBW)") (class "Default")
      (node (ref "C4") (pin "1") (pinfunction "1_1") (pintype "passive"))
      (node (ref "C8") (pin "1") (pinfunction "1_1") (pintype "passive"))
      (node (ref "D10") (pin "C") (pinfunction "C_C") (pintype "passive"))
      (node (ref "IC1") (pin "19") (pinfunction "VBW_19") (pintype "input"))
    )
    (net (code "44") (name "Net-(IC1-VSU)") (class "Default")
      (node (ref "C15") (pin "2") (pinfunction "2_2") (pintype "passive"))
      (node (ref "C6") (pin "2") (pinfunction "2_2") (pintype "passive"))
      (node (ref "IC1") (pin "12") (pinfunction "VSU_12") (pintype "input"))
    )
    (net (code "45") (name "Net-(IC1-VSV)") (class "Default")
      (node (ref "C14") (pin "2") (pinfunction "2_2") (pintype "passive"))
      (node (ref "C5") (pin "2") (pinfunction "2_2") (pintype "passive"))
      (node (ref "IC1") (pin "16") (pinfunction "VSV_16") (pintype "input"))
    )
    (net (code "46") (name "Net-(IC1-VSW)") (class "Default")
      (node (ref "C4") (pin "2") (pinfunction "2_2") (pintype "passive"))
      (node (ref "C8") (pin "2") (pinfunction "2_2") (pintype "passive"))
      (node (ref "IC1") (pin "20") (pinfunction "VSW_20") (pintype "input"))
    )
    (net (code "47") (name "Net-(IC2A-I)") (class "Default")
      (node (ref "C75") (pin "1") (pinfunction "1_1") (pintype "passive"))
      (node (ref "IC2") (pin "3") (pinfunction "I_3") (pintype "input"))
      (node (ref "OK3") (pin "6") (pinfunction "VO2_6") (pintype "passive"))
      (node (ref "R39") (pin "1") (pinfunction "1_1") (pintype "passive"))
    )
    (net (code "48") (name "Net-(IC2B-I)") (class "Default")
      (node (ref "C72") (pin "1") (pinfunction "1_1") (pintype "passive"))
      (node (ref "IC2") (pin "5") (pinfunction "I_5") (pintype "input"))
      (node (ref "OK2") (pin "6") (pinfunction "VO2_6") (pintype "passive"))
      (node (ref "R36") (pin "1") (pinfunction "1_1") (pintype "passive"))
    )
    (net (code "49") (name "Net-(IC2C-I)") (class "Default")
      (node (ref "C39") (pin "1") (pinfunction "1_1") (pintype "passive"))
      (node (ref "IC2") (pin "7") (pinfunction "I_7") (pintype "input"))
      (node (ref "OK1") (pin "6") (pinfunction "VO2_6") (pintype "passive"))
      (node (ref "R24") (pin "1") (pinfunction "1_1") (pintype "passive"))
    )
    (net (code "50") (name "Net-(IC2D-I)") (class "Default")
      (node (ref "C30") (pin "1") (pinfunction "1_1") (pintype "passive"))
      (node (ref "IC2") (pin "9") (pinfunction "I_9") (pintype "input"))
      (node (ref "OK1") (pin "7") (pinfunction "VO1_7") (pintype "passive"))
      (node (ref "R22") (pin "1") (pinfunction "1_1") (pintype "passive"))
    )
    (net (code "51") (name "Net-(IC2E-I)") (class "Default")
      (node (ref "C46") (pin "1") (pinfunction "1_1") (pintype "passive"))
      (node (ref "IC2") (pin "11") (pinfunction "I_11") (pintype "input"))
      (node (ref "OK2") (pin "7") (pinfunction "VO1_7") (pintype "passive"))
      (node (ref "R26") (pin "1") (pinfunction "1_1") (pintype "passive"))
    )
    (net (code "52") (name "Net-(IC2F-I)") (class "Default")
      (node (ref "C74") (pin "1") (pinfunction "1_1") (pintype "passive"))
      (node (ref "IC2") (pin "14") (pinfunction "I_14") (pintype "input"))
      (node (ref "OK3") (pin "7") (pinfunction "VO1_7") (pintype "passive"))
      (node (ref "R38") (pin "1") (pinfunction "1_1") (pintype "passive"))
    )
    (net (code "53") (name "Net-(IC3A-+IN)") (class "Default")
      (node (ref "IC3") (pin "3") (pinfunction "+IN_3") (pintype "input"))
      (node (ref "R97") (pin "1") (pinfunction "1_1") (pintype "passive"))
      (node (ref "R98") (pin "1") (pinfunction "1_1") (pintype "passive"))
    )
    (net (code "54") (name "Net-(IC3A--IN)") (class "Default")
      (node (ref "C32") (pin "1") (pinfunction "1_1") (pintype "passive"))
      (node (ref "IC3") (pin "2") (pinfunction "-IN_2") (pintype "input"))
      (node (ref "IC7") (pin "4") (pinfunction "A4_4") (pintype "passive"))
      (node (ref "R87") (pin "1") (pinfunction "1_1") (pintype "passive"))
    )
    (net (code "55") (name "Net-(IC3A-OUT)") (class "Default")
      (node (ref "C32") (pin "2") (pinfunction "2_2") (pintype "passive"))
      (node (ref "IC3") (pin "1") (pinfunction "OUT_1") (pintype "output"))
      (node (ref "R96") (pin "2") (pinfunction "2_2") (pintype "passive"))
    )
    (net (code "56") (name "Net-(IC3B-+IN)") (class "Default")
      (node (ref "IC3") (pin "5") (pinfunction "+IN_5") (pintype "input"))
      (node (ref "R79") (pin "1") (pinfunction "1_1") (pintype "passive"))
      (node (ref "R81") (pin "1") (pinfunction "1_1") (pintype "passive"))
    )
    (net (code "57") (name "Net-(IC3B--IN)") (class "Default")
      (node (ref "C34") (pin "1") (pinfunction "1_1") (pintype "passive"))
      (node (ref "IC3") (pin "6") (pinfunction "-IN_6") (pintype "input"))
      (node (ref "IC8") (pin "4") (pinfunction "A4_4") (pintype "passive"))
      (node (ref "R54") (pin "1") (pinfunction "1_1") (pintype "passive"))
    )
    (net (code "58") (name "Net-(IC3B-OUT)") (class "Default")
      (node (ref "C34") (pin "2") (pinfunction "2_2") (pintype "passive"))
      (node (ref "IC3") (pin "7") (pinfunction "OUT_7") (pintype "output"))
      (node (ref "R77") (pin "2") (pinfunction "2_2") (pintype "passive"))
    )
    (net (code "59") (name "Net-(IC3C-V+)") (class "Default")
      (node (ref "C33") (pin "2") (pinfunction "2_2") (pintype "passive"))
      (node (ref "IC3") (pin "8") (pinfunction "V+_8") (pintype "power_in"))
      (node (ref "R99") (pin "1") (pinfunction "1_1") (pintype "passive"))
    )
    (net (code "60") (name "Net-(IC4A-+IN)") (class "Default")
      (node (ref "IC4") (pin "3") (pinfunction "+IN_3") (pintype "input"))
      (node (ref "R37") (pin "1") (pinfunction "1_1") (pintype "passive"))
      (node (ref "R44") (pin "1") (pinfunction "1_1") (pintype "passive"))
    )
    (net (code "61") (name "Net-(IC4A--IN)") (class "Default")
      (node (ref "C38") (pin "1") (pinfunction "1_1") (pintype "passive"))
      (node (ref "IC4") (pin "2") (pinfunction "-IN_2") (pintype "input"))
      (node (ref "IC9") (pin "4") (pinfunction "A4_4") (pintype "passive"))
      (node (ref "R33") (pin "1") (pinfunction "1_1") (pintype "passive"))
    )
    (net (code "62") (name "Net-(IC4A-OUT)") (class "Default")
      (node (ref "C38") (pin "2") (pinfunction "2_2") (pintype "passive"))
      (node (ref "IC4") (pin "1") (pinfunction "OUT_1") (pintype "output"))
      (node (ref "R32") (pin "2") (pinfunction "2_2") (pintype "passive"))
    )
    (net (code "63") (name "Net-(IC4B-+IN)") (class "Default")
      (node (ref "C37") (pin "+") (pinfunction "+_+") (pintype "passive"))
      (node (ref "IC4") (pin "5") (pinfunction "+IN_5") (pintype "input"))
      (node (ref "R100") (pin "1") (pinfunction "1_1") (pintype "passive"))
      (node (ref "R101") (pin "2") (pinfunction "2_2") (pintype "passive"))
    )
    (net (code "64") (name "Net-(IC5A--IN)") (class "Default")
      (node (ref "C50") (pin "2") (pinfunction "2_2") (pintype "passive"))
      (node (ref "IC5") (pin "2") (pinfunction "-IN_2") (pintype "input"))
      (node (ref "IC7") (pin "6") (pinfunction "C6_6") (pintype "passive"))
      (node (ref "R60") (pin "2") (pinfunction "2_2") (pintype "passive"))
    )
    (net (code "65") (name "Net-(IC5B--IN)") (class "Default")
      (node (ref "C67") (pin "2") (pinfunction "2_2") (pintype "passive"))
      (node (ref "IC5") (pin "6") (pinfunction "-IN_6") (pintype "input"))
      (node (ref "IC8") (pin "6") (pinfunction "C6_6") (pintype "passive"))
      (node (ref "R61") (pin "2") (pinfunction "2_2") (pintype "passive"))
    )
    (net (code "66") (name "Net-(IC6A-+IN)") (class "Default")
      (node (ref "C69") (pin "2") (pinfunction "2_2") (pintype "passive"))
      (node (ref "IC6") (pin "3") (pinfunction "+IN_3") (pintype "input"))
      (node (ref "IC9") (pin "6") (pinfunction "C6_6") (pintype "passive"))
      (node (ref "R62") (pin "2") (pinfunction "2_2") (pintype "passive"))
    )
    (net (code "67") (name "Net-(IC6B--IN)") (class "Default")
      (node (ref "IC6") (pin "6") (pinfunction "-IN_6") (pintype "input"))
      (node (ref "IC6") (pin "7") (pinfunction "OUT_7") (pintype "output"))
    )
    (net (code "68") (name "Net-(IC7-A2)") (class "Default")
      (node (ref "IC7") (pin "2") (pinfunction "A2_2") (pintype "passive"))
      (node (ref "R96") (pin "1") (pinfunction "1_1") (pintype "passive"))
    )
    (net (code "69") (name "Net-(IC8-A2)") (class "Default")
      (node (ref "IC8") (pin "2") (pinfunction "A2_2") (pintype "passive"))
      (node (ref "R77") (pin "1") (pinfunction "1_1") (pintype "passive"))
    )
    (net (code "70") (name "Net-(IC9-A2)") (class "Default")
      (node (ref "IC9") (pin "2") (pinfunction "A2_2") (pintype "passive"))
      (node (ref "R32") (pin "1") (pinfunction "1_1") (pintype "passive"))
    )
    (net (code "71") (name "Net-(IC10A-+IN)") (class "Default")
      (node (ref "IC10") (pin "3") (pinfunction "+IN_3") (pintype "input"))
      (node (ref "R53") (pin "2") (pinfunction "2_2") (pintype "passive"))
      (node (ref "R92") (pin "1") (pinfunction "1_1") (pintype "passive"))
    )
    (net (code "72") (name "Net-(IC10A--IN)") (class "Default")
      (node (ref "IC10") (pin "2") (pinfunction "-IN_2") (pintype "input"))
      (node (ref "IC12") (pin "4") (pinfunction "A4_4") (pintype "passive"))
      (node (ref "R90") (pin "1") (pinfunction "1_1") (pintype "passive"))
      (node (ref "R93") (pin "1") (pinfunction "1_1") (pintype "passive"))
    )
    (net (code "73") (name "Net-(IC10A-OUT)") (class "Default")
      (node (ref "IC10") (pin "1") (pinfunction "OUT_1") (pintype "output"))
      (node (ref "R89") (pin "2") (pinfunction "2_2") (pintype "passive"))
      (node (ref "R90") (pin "2") (pinfunction "2_2") (pintype "passive"))
    )
    (net (code "74") (name "Net-(IC10B-+IN)") (class "Default")
      (node (ref "C24") (pin "+") (pinfunction "+_+") (pintype "passive"))
      (node (ref "IC10") (pin "5") (pinfunction "+IN_5") (pintype "input"))
      (node (ref "R94") (pin "2") (pinfunction "2_2") (pintype "passive"))
      (node (ref "R95") (pin "1") (pinfunction "1_1") (pintype "passive"))
    )
    (net (code "75") (name "Net-(IC10B--IN)") (class "Default")
      (node (ref "C12") (pin "+") (pinfunction "+_+") (pintype "passive"))
      (node (ref "IC10") (pin "6") (pinfunction "-IN_6") (pintype "input"))
      (node (ref "IC10") (pin "7") (pinfunction "OUT_7") (pintype "output"))
      (node (ref "R92") (pin "2") (pinfunction "2_2") (pintype "passive"))
    )
    (net (code "76") (name "Net-(IC10C-V+)") (class "Default")
      (node (ref "C53") (pin "1") (pinfunction "1_1") (pintype "passive"))
      (node (ref "IC10") (pin "8") (pinfunction "V+_8") (pintype "power_in"))
      (node (ref "IC12") (pin "3") (pinfunction "C3_3") (pintype "passive"))
      (node (ref "R91") (pin "2") (pinfunction "2_2") (pintype "passive"))
    )
    (net (code "77") (name "Net-(IC11A--IN)") (class "Default")
      (node (ref "C61") (pin "2") (pinfunction "2_2") (pintype "passive"))
      (node (ref "IC11") (pin "2") (pinfunction "-IN_2") (pintype "input"))
      (node (ref "IC12") (pin "6") (pinfunction "C6_6") (pintype "passive"))
      (node (ref "R88") (pin "2") (pinfunction "2_2") (pintype "passive"))
    )
    (net (code "78") (name "Net-(IC11B--IN)") (class "Default")
      (node (ref "IC11") (pin "6") (pinfunction "-IN_6") (pintype "input"))
      (node (ref "IC11") (pin "7") (pinfunction "OUT_7") (pintype "output"))
    )
    (net (code "79") (name "Net-(IC11C-V+)") (class "Default")
      (node (ref "C70") (pin "2") (pinfunction "2_2") (pintype "passive"))
      (node (ref "IC11") (pin "8") (pinfunction "V+_8") (pintype "power_in"))
      (node (ref "R80") (pin "2") (pinfunction "2_2") (pintype "passive"))
    )
    (net (code "80") (name "Net-(IC12-A2)") (class "Default")
      (node (ref "IC12") (pin "2") (pinfunction "A2_2") (pintype "passive"))
      (node (ref "R89") (pin "1") (pinfunction "1_1") (pintype "passive"))
    )
    (net (code "81") (name "Net-(IC13-ANODE)") (class "Default")
      (node (ref "IC13") (pin "2") (pinfunction "ANODE_2") (pintype "bidirectional"))
      (node (ref "R16") (pin "2") (pinfunction "2_2") (pintype "passive"))
    )
    (net (code "82") (name "Net-(IC13-VO_1)") (class "Default")
      (node (ref "IC13") (pin "6") (pinfunction "VO_1_6") (pintype "bidirectional"))
      (node (ref "IC13") (pin "7") (pinfunction "VO_2_7") (pintype "bidirectional"))
      (node (ref "IC15") (pin "13") (pinfunction "I_13") (pintype "input"))
      (node (ref "R66") (pin "1") (pinfunction "1_1") (pintype "passive"))
    )
    (net (code "83") (name "Net-(IC14-ANODE)") (class "Default")
      (node (ref "IC14") (pin "2") (pinfunction "ANODE_2") (pintype "bidirectional"))
      (node (ref "R15") (pin "2") (pinfunction "2_2") (pintype "passive"))
    )
    (net (code "84") (name "Net-(IC14-VO_1)") (class "Default")
      (node (ref "IC14") (pin "6") (pinfunction "VO_1_6") (pintype "bidirectional"))
      (node (ref "IC14") (pin "7") (pinfunction "VO_2_7") (pintype "bidirectional"))
      (node (ref "IC15") (pin "11") (pinfunction "I_11") (pintype "input"))
      (node (ref "R65") (pin "1") (pinfunction "1_1") (pintype "passive"))
    )
    (net (code "85") (name "Net-(IC15A-O)") (class "Default")
      (node (ref "IC15") (pin "12") (pinfunction "O_12") (pintype "output"))
      (node (ref "R67") (pin "2") (pinfunction "2_2") (pintype "passive"))
      (node (ref "R69") (pin "2") (pinfunction "2_2") (pintype "passive"))
    )
    (net (code "86") (name "Net-(IC15B-O)") (class "Default")
      (node (ref "IC15") (pin "10") (pinfunction "O_10") (pintype "output"))
      (node (ref "R68") (pin "2") (pinfunction "2_2") (pintype "passive"))
    )
    (net (code "87") (name "Net-(IC15C-I)") (class "Default")
      (node (ref "IC15") (pin "8") (pinfunction "O_8") (pintype "output"))
      (node (ref "IC15") (pin "9") (pinfunction "I_9") (pintype "input"))
    )
    (net (code "88") (name "Net-(IC15D-I)") (class "Default")
      (node (ref "IC15") (pin "1") (pinfunction "I_1") (pintype "input"))
      (node (ref "IC15") (pin "2") (pinfunction "O_2") (pintype "output"))
    )
    (net (code "89") (name "Net-(IC15E-I)") (class "Default")
      (node (ref "IC15") (pin "3") (pinfunction "I_3") (pintype "input"))
      (node (ref "IC15") (pin "4") (pinfunction "O_4") (pintype "output"))
    )
    (net (code "90") (name "Net-(IC15F-I)") (class "Default")
      (node (ref "IC15") (pin "5") (pinfunction "I_5") (pintype "input"))
      (node (ref "IC15") (pin "6") (pinfunction "O_6") (pintype "output"))
    )
    (net (code "91") (name "Net-(IC18-IN)") (class "Default")
      (node (ref "C58") (pin "1") (pinfunction "1_1") (pintype "passive"))
      (node (ref "C64") (pin "1") (pinfunction "1_1") (pintype "passive"))
      (node (ref "D15") (pin "C") (pinfunction "C_C") (pintype "passive"))
      (node (ref "IC18") (pin "3") (pinfunction "IN_3") (pintype "bidirectional"))
      (node (ref "LD3") (pin "A") (pinfunction "A_A") (pintype "passive"))
      (node (ref "U$1") (pin "3") (pinfunction "IN_3") (pintype "bidirectional"))
    )
    (net (code "92") (name "Net-(IC19-DC)") (class "Default")
      (node (ref "IC19") (pin "1") (pinfunction "SWC_1") (pintype "passive"))
      (node (ref "IC19") (pin "7") (pinfunction "IS_7") (pintype "passive"))
      (node (ref "IC19") (pin "8") (pinfunction "DC_8") (pintype "passive"))
      (node (ref "R84") (pin "2") (pinfunction "2_2") (pintype "passive"))
    )
    (net (code "93") (name "Net-(IC19-FB)") (class "Default")
      (node (ref "IC19") (pin "5") (pinfunction "FB_5") (pintype "passive"))
      (node (ref "R85") (pin "2") (pinfunction "2_2") (pintype "passive"))
      (node (ref "R86") (pin "2") (pinfunction "2_2") (pintype "passive"))
    )
    (net (code "94") (name "Net-(IC19-SWE)") (class "Default")
      (node (ref "D14") (pin "C") (pinfunction "C_C") (pintype "passive"))
      (node (ref "IC19") (pin "2") (pinfunction "SWE_2") (pintype "passive"))
      (node (ref "L1") (pin "1") (pinfunction "1_1") (pintype "passive"))
    )
    (net (code "95") (name "Net-(IC19-TC)") (class "Default")
      (node (ref "C40") (pin "1") (pinfunction "1_1") (pintype "passive"))
      (node (ref "IC19") (pin "3") (pinfunction "TC_3") (pintype "passive"))
    )
    (net (code "96") (name "Net-(IC19-VCC)") (class "Default")
      (node (ref "C35") (pin "+") (pinfunction "+_+") (pintype "passive"))
      (node (ref "D13") (pin "C") (pinfunction "C_C") (pintype "passive"))
      (node (ref "IC19") (pin "6") (pinfunction "VCC_6") (pintype "passive"))
      (node (ref "LD2") (pin "A") (pinfunction "A_A") (pintype "passive"))
      (node (ref "R84") (pin "1") (pinfunction "1_1") (pintype "passive"))
    )
    (net (code "97") (name "Net-(K3-PadCOM)") (class "Default")
      (node (ref "K3") (pin "COM") (pinfunction "COM_COM") (pintype "passive"))
      (node (ref "X4") (pin "1") (pinfunction "1_1") (pintype "passive"))
    )
    (net (code "98") (name "Net-(LD2-PadC)") (class "Default")
      (node (ref "LD2") (pin "C") (pinfunction "C_C") (pintype "passive"))
      (node (ref "R82") (pin "2") (pinfunction "2_2") (pintype "passive"))
    )
    (net (code "99") (name "Net-(LD3-PadC)") (class "Default")
      (node (ref "LD3") (pin "C") (pinfunction "C_C") (pintype "passive"))
      (node (ref "R83") (pin "2") (pinfunction "2_2") (pintype "passive"))
    )
    (net (code "100") (name "Net-(OK1A-A1)") (class "Default")
      (node (ref "OK1") (pin "1") (pinfunction "A1_1") (pintype "passive"))
      (node (ref "OK1") (pin "3") (pinfunction "C2_3") (pintype "passive"))
      (node (ref "R29") (pin "2") (pinfunction "2_2") (pintype "passive"))
    )
    (net (code "101") (name "Net-(OK2A-A1)") (class "Default")
      (node (ref "OK2") (pin "1") (pinfunction "A1_1") (pintype "passive"))
      (node (ref "OK2") (pin "3") (pinfunction "C2_3") (pintype "passive"))
      (node (ref "R28") (pin "2") (pinfunction "2_2") (pintype "passive"))
    )
    (net (code "102") (name "Net-(OK3A-A1)") (class "Default")
      (node (ref "OK3") (pin "1") (pinfunction "A1_1") (pintype "passive"))
      (node (ref "OK3") (pin "3") (pinfunction "C2_3") (pintype "passive"))
      (node (ref "R27") (pin "2") (pinfunction "2_2") (pintype "passive"))
    )
    (net (code "103") (name "Net-(OK4A-C1)") (class "Default")
      (node (ref "OK4") (pin "2") (pinfunction "C1_2") (pintype "passive"))
      (node (ref "R31") (pin "1") (pinfunction "1_1") (pintype "passive"))
    )
    (net (code "104") (name "Net-(Q1-PadB)") (class "Default")
      (node (ref "Q1") (pin "B") (pinfunction "B_B") (pintype "passive"))
      (node (ref "R34") (pin "1") (pinfunction "1_1") (pintype "passive"))
    )
    (net (code "105") (name "Net-(Q1-PadC)") (class "Default")
      (node (ref "Q1") (pin "C") (pinfunction "C_C") (pintype "passive"))
      (node (ref "R31") (pin "2") (pinfunction "2_2") (pintype "passive"))
    )
    (net (code "106") (name "Net-(Q3-PadB)") (class "Default")
      (node (ref "Q3") (pin "B") (pinfunction "B_B") (pintype "passive"))
      (node (ref "R68") (pin "1") (pinfunction "1_1") (pintype "passive"))
    )
    (net (code "107") (name "Net-(R35-Pad1)") (class "Default")
      (node (ref "R35") (pin "1") (pinfunction "1_1") (pintype "passive"))
      (node (ref "R47") (pin "2") (pinfunction "2_2") (pintype "passive"))
    )
    (net (code "108") (name "Net-(R35-Pad2)") (class "Default")
      (node (ref "R35") (pin "2") (pinfunction "2_2") (pintype "passive"))
      (node (ref "R49") (pin "1") (pinfunction "1_1") (pintype "passive"))
    )
    (net (code "109") (name "Net-(R47-Pad1)") (class "Default")
      (node (ref "R47") (pin "1") (pinfunction "1_1") (pintype "passive"))
      (node (ref "R48") (pin "2") (pinfunction "2_2") (pintype "passive"))
    )
    (net (code "110") (name "Net-(R48-Pad1)") (class "Default")
      (node (ref "R48") (pin "1") (pinfunction "1_1") (pintype "passive"))
      (node (ref "R50") (pin "2") (pinfunction "2_2") (pintype "passive"))
    )
    (net (code "111") (name "Net-(R50-Pad1)") (class "Default")
      (node (ref "R50") (pin "1") (pinfunction "1_1") (pintype "passive"))
      (node (ref "R51") (pin "2") (pinfunction "2_2") (pintype "passive"))
    )
    (net (code "112") (name "Net-(R73-Pad2)") (class "Default")
      (node (ref "R73") (pin "2") (pinfunction "2_2") (pintype "passive"))
      (node (ref "R75") (pin "1") (pinfunction "1_1") (pintype "passive"))
    )
    (net (code "113") (name "Net-(U$2B-IN+)") (class "Default")
      (node (ref "C42") (pin "1") (pinfunction "1_1") (pintype "passive"))
      (node (ref "R56") (pin "2") (pinfunction "2_2") (pintype "passive"))
      (node (ref "R57") (pin "2") (pinfunction "2_2") (pintype "passive"))
      (node (ref "R78") (pin "2") (pinfunction "2_2") (pintype "passive"))
      (node (ref "U$2") (pin "4") (pinfunction "IN+_4") (pintype "input"))
    )
    (net (code "114") (name "Net-(X2B-1)") (class "Default")
      (node (ref "D3") (pin "A") (pinfunction "A_A") (pintype "passive"))
      (node (ref "Q2") (pin "D") (pinfunction "D_D") (pintype "passive"))
      (node (ref "X2") (pin "2") (pinfunction "1_2") (pintype "passive"))
    )
    (net (code "115") (name "Net-(X4B-1)") (class "Default")
      (node (ref "K3") (pin "NC") (pinfunction "NC_NC") (pintype "passive"))
      (node (ref "X4") (pin "2") (pinfunction "1_2") (pintype "passive"))
    )
    (net (code "116") (name "PWM_U_H") (class "Default")
      (node (ref "R29") (pin "1") (pinfunction "1_1") (pintype "passive"))
      (node (ref "SV1") (pin "4") (pinfunction "4_4") (pintype "passive"))
    )
    (net (code "117") (name "PWM_U_L") (class "Default")
      (node (ref "OK1") (pin "2") (pinfunction "C1_2") (pintype "passive"))
      (node (ref "OK1") (pin "4") (pinfunction "A2_4") (pintype "passive"))
      (node (ref "SV1") (pin "3") (pinfunction "3_3") (pintype "passive"))
    )
    (net (code "118") (name "PWM_V_H") (class "Default")
      (node (ref "R28") (pin "1") (pinfunction "1_1") (pintype "passive"))
      (node (ref "SV1") (pin "6") (pinfunction "6_6") (pintype "passive"))
    )
    (net (code "119") (name "PWM_V_L") (class "Default")
      (node (ref "OK2") (pin "2") (pinfunction "C1_2") (pintype "passive"))
      (node (ref "OK2") (pin "4") (pinfunction "A2_4") (pintype "passive"))
      (node (ref "SV1") (pin "5") (pinfunction "5_5") (pintype "passive"))
    )
    (net (code "120") (name "PWM_W_H") (class "Default")
      (node (ref "R27") (pin "1") (pinfunction "1_1") (pintype "passive"))
      (node (ref "SV1") (pin "8") (pinfunction "8_8") (pintype "passive"))
    )
    (net (code "121") (name "PWM_W_L") (class "Default")
      (node (ref "OK3") (pin "2") (pinfunction "C1_2") (pintype "passive"))
      (node (ref "OK3") (pin "4") (pinfunction "A2_4") (pintype "passive"))
      (node (ref "SV1") (pin "7") (pinfunction "7_7") (pintype "passive"))
    )
    (net (code "122") (name "RLY_FLT") (class "Default")
      (node (ref "R55") (pin "2") (pinfunction "2_2") (pintype "passive"))
      (node (ref "R56") (pin "1") (pinfunction "1_1") (pintype "passive"))
      (node (ref "SV1") (pin "13") (pinfunction "13_13") (pintype "passive"))
      (node (ref "U$2") (pin "1") (pinfunction "OUT_1") (pintype "output"))
    )
    (net (code "123") (name "SFT_ST") (class "Default")
      (node (ref "R15") (pin "1") (pinfunction "1_1") (pintype "passive"))
      (node (ref "SV1") (pin "14") (pinfunction "14_14") (pintype "passive"))
    )
    (net (code "124") (name "U_PWM") (class "Default")
      (node (ref "IC1") (pin "24") (pinfunction "U_24") (pintype "output"))
      (node (ref "X3") (pin "1") (pinfunction "1_1") (pintype "passive"))
    )
    (net (code "125") (name "VCCIO") (class "Default")
      (node (ref "C36") (pin "1") (pinfunction "1_1") (pintype "passive"))
      (node (ref "C41") (pin "1") (pinfunction "1_1") (pintype "passive"))
      (node (ref "C62") (pin "2") (pinfunction "2_2") (pintype "passive"))
      (node (ref "C71") (pin "1") (pinfunction "1_1") (pintype "passive"))
      (node (ref "JP1") (pin "3") (pinfunction "3_3") (pintype "passive"))
      (node (ref "JP1") (pin "4") (pinfunction "4_4") (pintype "passive"))
      (node (ref "OK4") (pin "8") (pinfunction "VCC_8") (pintype "passive"))
      (node (ref "R30") (pin "1") (pinfunction "1_1") (pintype "passive"))
      (node (ref "R55") (pin "1") (pinfunction "1_1") (pintype "passive"))
      (node (ref "R57") (pin "1") (pinfunction "1_1") (pintype "passive"))
      (node (ref "R58") (pin "2") (pinfunction "2_2") (pintype "passive"))
      (node (ref "R59") (pin "1") (pinfunction "1_1") (pintype "passive"))
      (node (ref "R80") (pin "1") (pinfunction "1_1") (pintype "passive"))
      (node (ref "U$2") (pin "5") (pinfunction "VCC_5") (pintype "power_in"))
    )
    (net (code "126") (name "VDC+") (class "Default")
      (node (ref "C3") (pin "1") (pinfunction "1_1") (pintype "passive"))
      (node (ref "D3") (pin "K") (pinfunction "K_K") (pintype "passive"))
      (node (ref "IC1") (pin "27") (pinfunction "P_27") (pintype "input"))
      (node (ref "R49") (pin "2") (pinfunction "2_2") (pintype "passive"))
      (node (ref "X1") (pin "2") (pinfunction "1_2") (pintype "passive"))
      (node (ref "X2") (pin "1") (pinfunction "1_1") (pintype "passive"))
    )
    (net (code "127") (name "VFO") (class "Default")
      (node (ref "IC1") (pin "6") (pinfunction "VFO_6") (pintype "output"))
      (node (ref "R34") (pin "2") (pinfunction "2_2") (pintype "passive"))
    )
    (net (code "128") (name "VOLT_SENS") (class "Default")
      (node (ref "C61") (pin "1") (pinfunction "1_1") (pintype "passive"))
      (node (ref "IC11") (pin "1") (pinfunction "OUT_1") (pintype "output"))
      (node (ref "R88") (pin "1") (pinfunction "1_1") (pintype "passive"))
      (node (ref "SV1") (pin "18") (pinfunction "18_18") (pintype "passive"))
    )
    (net (code "129") (name "V_PWM") (class "Default")
      (node (ref "IC1") (pin "25") (pinfunction "V_25") (pintype "output"))
      (node (ref "X3") (pin "2") (pinfunction "1_2") (pintype "passive"))
    )
    (net (code "130") (name "W_PWM") (class "Default")
      (node (ref "IC1") (pin "26") (pinfunction "W_26") (pintype "output"))
      (node (ref "X3") (pin "3") (pinfunction "1_3") (pintype "passive"))
    )
    (net (code "131") (name "unconnected-(J1-PadP1)") (class "Default")
      (node (ref "J1") (pin "P1") (pinfunction "P1_P1") (pintype "passive"))
    )
    (net (code "132") (name "unconnected-(J1-PadP2)") (class "Default")
      (node (ref "J1") (pin "P2") (pinfunction "P2_P2") (pintype "passive"))
    )
    (net (code "133") (name "unconnected-(J1-PadP3)") (class "Default")
      (node (ref "J1") (pin "P3") (pinfunction "P3_P3") (pintype "passive"))
    )
    (net (code "134") (name "unconnected-(J1-PadP4)") (class "Default")
      (node (ref "J1") (pin "P4") (pinfunction "P4_P4") (pintype "passive"))
    )
    (net (code "135") (name "unconnected-(J1-PadP5)") (class "Default")
      (node (ref "J1") (pin "P5") (pinfunction "P5_P5") (pintype "passive"))
    )
    (net (code "136") (name "unconnected-(J1-PadP6)") (class "Default")
      (node (ref "J1") (pin "P6") (pinfunction "P6_P6") (pintype "passive"))
    )
    (net (code "137") (name "unconnected-(J1-PadP7)") (class "Default")
      (node (ref "J1") (pin "P7") (pinfunction "P7_P7") (pintype "passive"))
    )
    (net (code "138") (name "unconnected-(J1-PadP8)") (class "Default")
      (node (ref "J1") (pin "P8") (pinfunction "P8_P8") (pintype "passive"))
    )
    (net (code "139") (name "unconnected-(J1-PadP9)") (class "Default")
      (node (ref "J1") (pin "P9") (pinfunction "P9_P9") (pintype "passive"))
    )
    (net (code "140") (name "unconnected-(J1-PadP10)") (class "Default")
      (node (ref "J1") (pin "P10") (pinfunction "P10_P10") (pintype "passive"))
    )
    (net (code "141") (name "unconnected-(J1-PadP11)") (class "Default")
      (node (ref "J1") (pin "P11") (pinfunction "P11_P11") (pintype "passive"))
    )
    (net (code "142") (name "unconnected-(J1-PadP12)") (class "Default")
      (node (ref "J1") (pin "P12") (pinfunction "P12_P12") (pintype "passive"))
    )
    (net (code "143") (name "unconnected-(JP1-Pad1)") (class "Default")
      (node (ref "JP1") (pin "1") (pinfunction "1_1") (pintype "passive"))
    )
    (net (code "144") (name "unconnected-(JP1-Pad5)") (class "Default")
      (node (ref "JP1") (pin "5") (pinfunction "5_5") (pintype "passive"))
    )
    (net (code "145") (name "unconnected-(K3-PadNO)") (class "Default")
      (node (ref "K3") (pin "NO") (pinfunction "NO_NO") (pintype "passive"))
    )
    (net (code "146") (name "unconnected-(OK4B-A2-Pad4)") (class "Default")
      (node (ref "OK4") (pin "4") (pinfunction "A2_4") (pintype "passive"))
    )
    (net (code "147") (name "unconnected-(OK4B-C2-Pad3)") (class "Default")
      (node (ref "OK4") (pin "3") (pinfunction "C2_3") (pintype "passive"))
    )
    (net (code "148") (name "unconnected-(OK4B-VO2-Pad6)") (class "Default")
      (node (ref "OK4") (pin "6") (pinfunction "VO2_6") (pintype "passive"))
    )
    (net (code "149") (name "unconnected-(P1-Pad2)") (class "Default")
      (node (ref "P1") (pin "2") (pinfunction "2_2") (pintype "passive"))
    )
    (net (code "150") (name "unconnected-(P2-Pad2)") (class "Default")
      (node (ref "P2") (pin "2") (pinfunction "2_2") (pintype "passive"))
    )
    (net (code "151") (name "unconnected-(P3-Pad2)") (class "Default")
      (node (ref "P3") (pin "2") (pinfunction "2_2") (pintype "passive"))
    )
    (net (code "152") (name "unconnected-(P4-Pad2)") (class "Default")
      (node (ref "P4") (pin "2") (pinfunction "2_2") (pintype "passive"))
    )
    (net (code "153") (name "unconnected-(P5-Pad2)") (class "Default")
      (node (ref "P5") (pin "2") (pinfunction "2_2") (pintype "passive"))
    )
    (net (code "154") (name "unconnected-(P6-Pad2)") (class "Default")
      (node (ref "P6") (pin "2") (pinfunction "2_2") (pintype "passive"))
    )
  )
)
